# LARIX_V3_finish.net
KiCad netlist of a schematic drawn in EAGLE
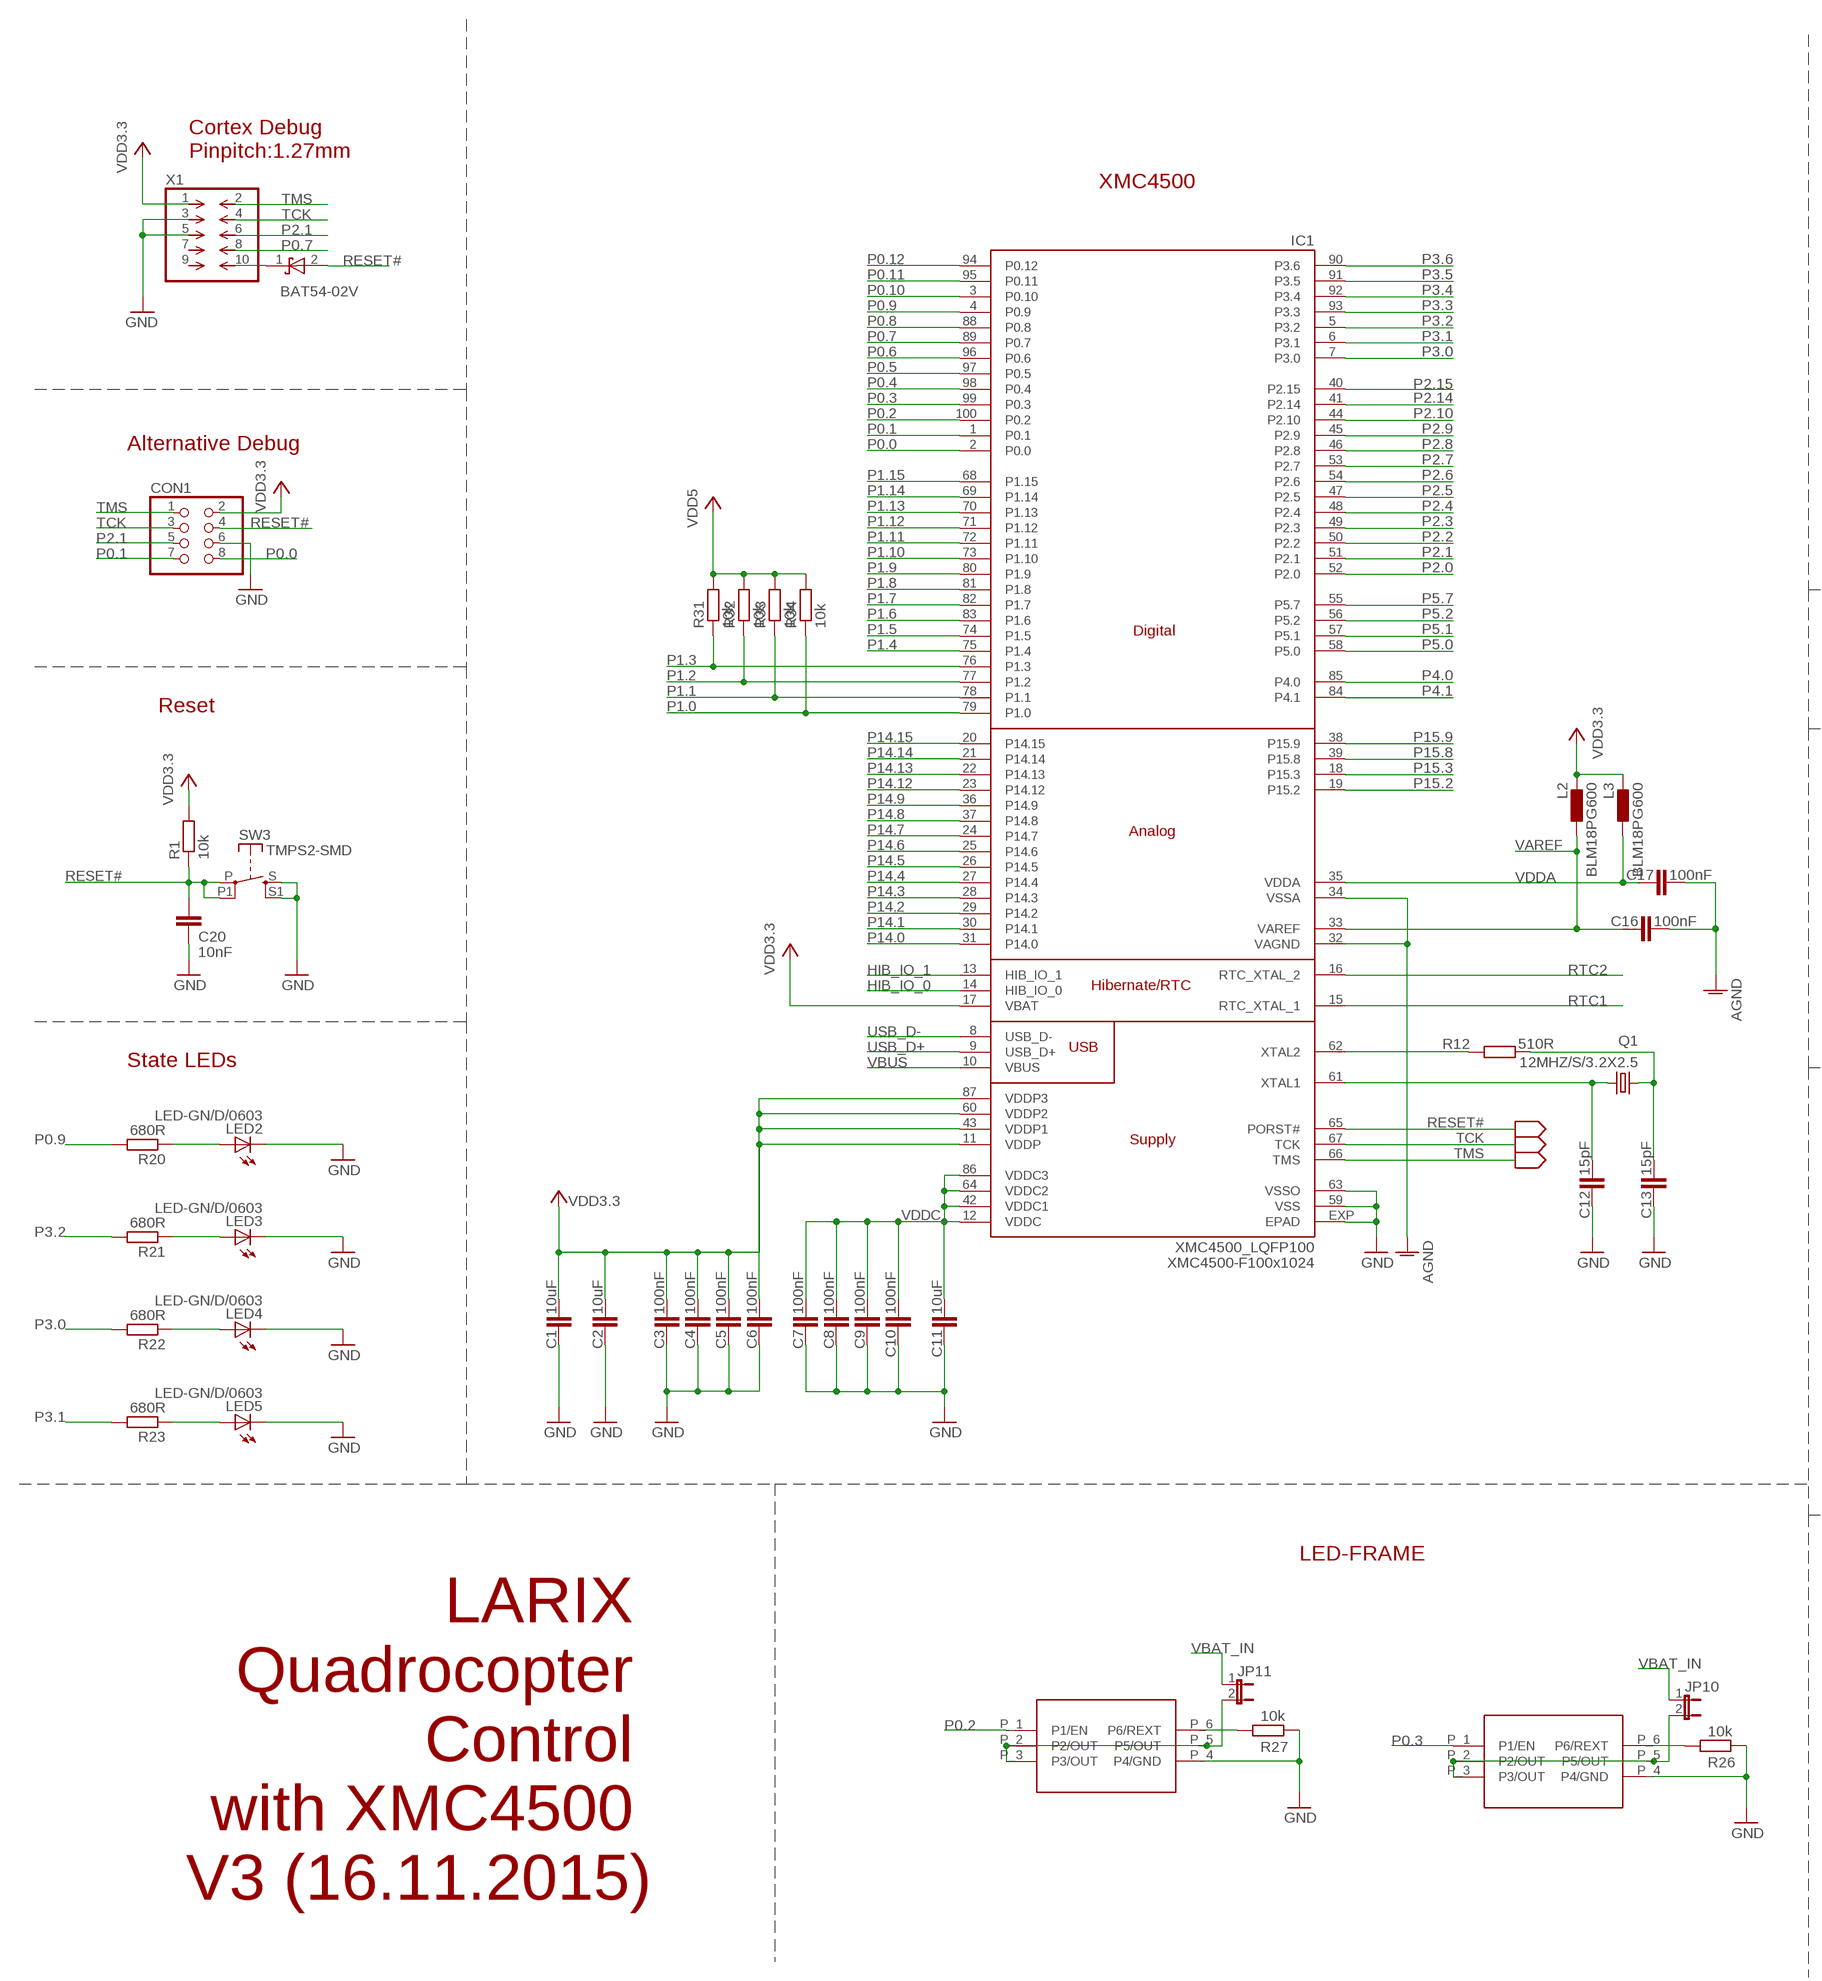
[diagram p0: schematic, sheet 1, part 1 of 2]
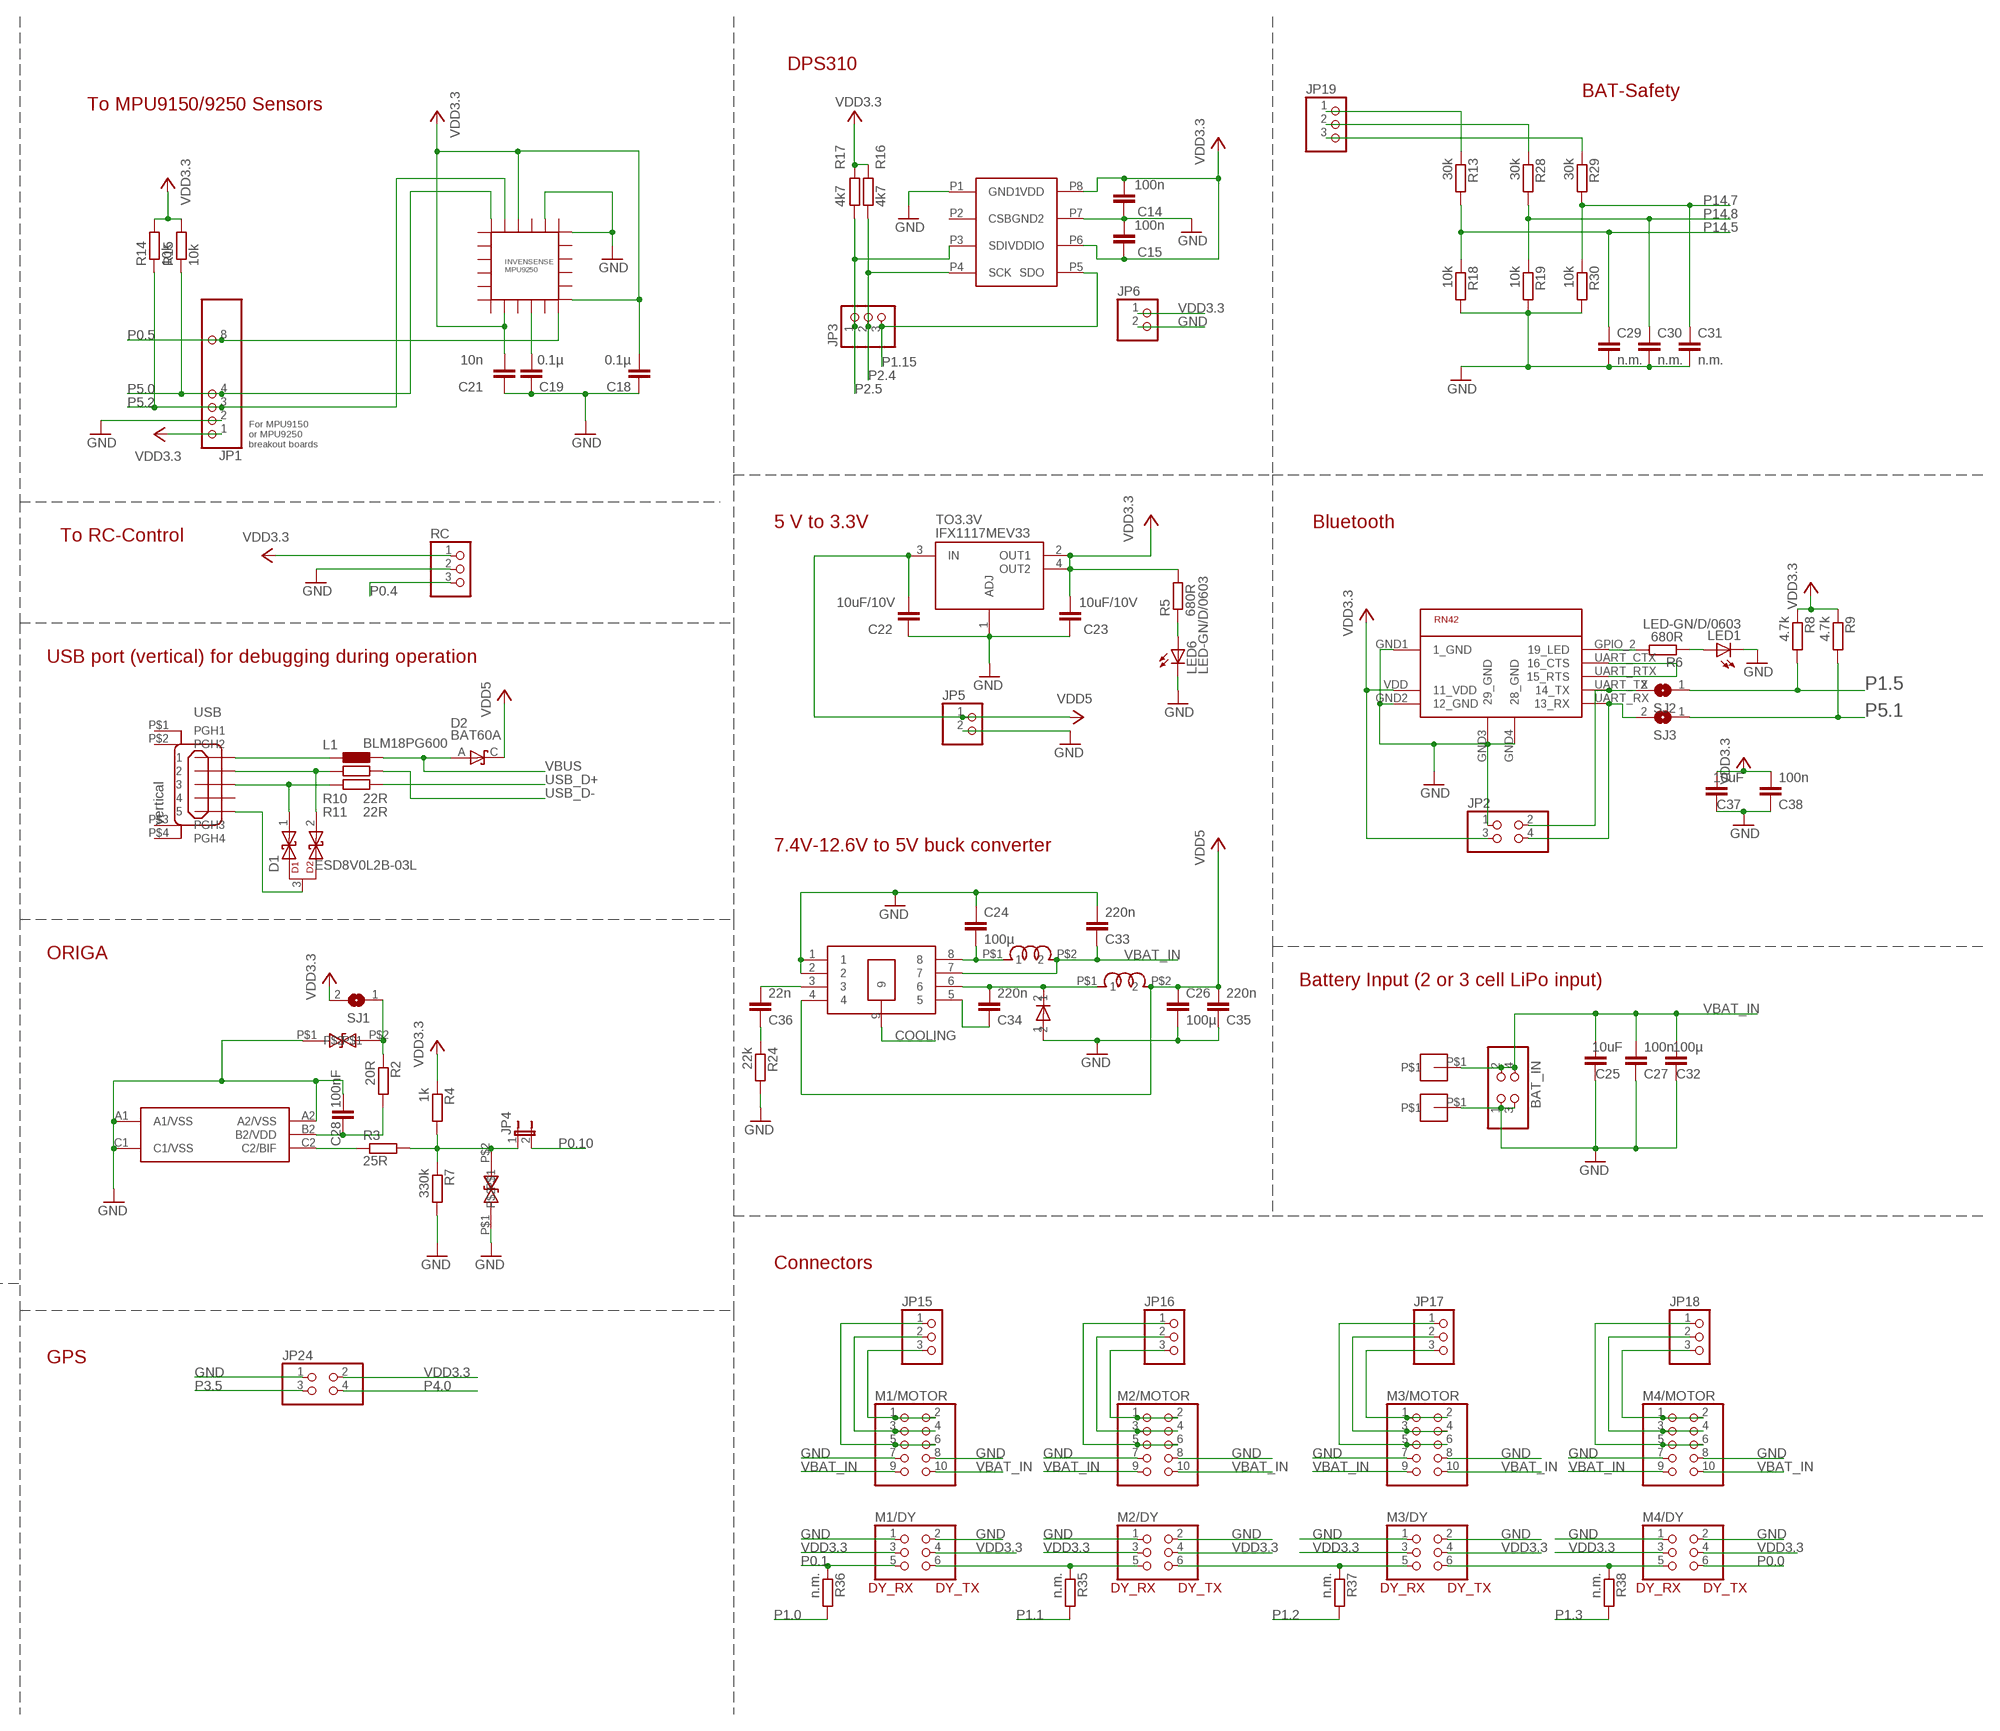
[diagram p1: schematic, sheet 1, part 2 of 2]

(export (version "E")
  (design (tool "Eeschema 10.0.6"))
  (components
    (comp (ref "47UH")
      (value "WUERTH47UFCHOKE")
      (footprint "eagle-import:INDUCTANCEWUERTZ47UH")
      (libsource (lib "eagle-import") (part "WUERTH47UFCHOKE"))
    )
    (comp (ref "47µH")
      (value "WUERTH47UFCHOKE")
      (footprint "eagle-import:INDUCTANCEWUERTZ47UH")
      (libsource (lib "eagle-import") (part "WUERTH47UFCHOKE"))
    )
    (comp (ref "BAT_IN")
      (value "PINHD-2X2")
      (footprint "eagle-import:2X02")
      (libsource (lib "eagle-import") (part "PINHD-2X2"))
    )
    (comp (ref "C1")
      (value "10uF")
      (footprint "eagle-import:C0805K")
      (libsource (lib "eagle-import") (part "C-EUC0805K"))
    )
    (comp (ref "C2")
      (value "10uF")
      (footprint "eagle-import:C0805K")
      (libsource (lib "eagle-import") (part "C-EUC0805K"))
    )
    (comp (ref "C3")
      (value "100nF")
      (footprint "eagle-import:C0603")
      (libsource (lib "eagle-import") (part "resistor_C-EUC0603"))
    )
    (comp (ref "C4")
      (value "100nF")
      (footprint "eagle-import:C0603")
      (libsource (lib "eagle-import") (part "resistor_C-EUC0603"))
    )
    (comp (ref "C5")
      (value "100nF")
      (footprint "eagle-import:C0603")
      (libsource (lib "eagle-import") (part "resistor_C-EUC0603"))
    )
    (comp (ref "C6")
      (value "100nF")
      (footprint "eagle-import:C0603")
      (libsource (lib "eagle-import") (part "resistor_C-EUC0603"))
    )
    (comp (ref "C7")
      (value "100nF")
      (footprint "eagle-import:C0603")
      (libsource (lib "eagle-import") (part "resistor_C-EUC0603"))
    )
    (comp (ref "C8")
      (value "100nF")
      (footprint "eagle-import:C0603")
      (libsource (lib "eagle-import") (part "resistor_C-EUC0603"))
    )
    (comp (ref "C9")
      (value "100nF")
      (footprint "eagle-import:C0603")
      (libsource (lib "eagle-import") (part "resistor_C-EUC0603"))
    )
    (comp (ref "C10")
      (value "100nF")
      (footprint "eagle-import:C0603")
      (libsource (lib "eagle-import") (part "resistor_C-EUC0603"))
    )
    (comp (ref "C11")
      (value "10uF")
      (footprint "eagle-import:C0805K")
      (libsource (lib "eagle-import") (part "C-EUC0805K"))
    )
    (comp (ref "C12")
      (value "15pF")
      (footprint "eagle-import:C0603")
      (libsource (lib "eagle-import") (part "resistor_C-EUC0603"))
    )
    (comp (ref "C13")
      (value "15pF")
      (footprint "eagle-import:C0603")
      (libsource (lib "eagle-import") (part "resistor_C-EUC0603"))
    )
    (comp (ref "C14")
      (value "100n")
      (footprint "eagle-import:C0603")
      (libsource (lib "eagle-import") (part "resistor_C-EUC0603"))
    )
    (comp (ref "C15")
      (value "100n")
      (footprint "eagle-import:C0603")
      (libsource (lib "eagle-import") (part "resistor_C-EUC0603"))
    )
    (comp (ref "C16")
      (value "100nF")
      (footprint "eagle-import:C0603")
      (libsource (lib "eagle-import") (part "resistor_C-EUC0603"))
    )
    (comp (ref "C17")
      (value "100nF")
      (footprint "eagle-import:C0603")
      (libsource (lib "eagle-import") (part "resistor_C-EUC0603"))
    )
    (comp (ref "C18")
      (value "0.1µ")
      (footprint "eagle-import:C0603")
      (libsource (lib "eagle-import") (part "resistor_C-EUC0603"))
    )
    (comp (ref "C19")
      (value "0.1µ")
      (footprint "eagle-import:C0603")
      (libsource (lib "eagle-import") (part "resistor_C-EUC0603"))
    )
    (comp (ref "C20")
      (value "10nF")
      (footprint "eagle-import:C0603")
      (libsource (lib "eagle-import") (part "resistor_C-EUC0603"))
    )
    (comp (ref "C21")
      (value "10n")
      (footprint "eagle-import:C0603")
      (libsource (lib "eagle-import") (part "resistor_C-EUC0603"))
    )
    (comp (ref "C22")
      (value "10uF/10V")
      (footprint "eagle-import:C0805K")
      (libsource (lib "eagle-import") (part "C-EUC0805K"))
    )
    (comp (ref "C23")
      (value "10uF/10V")
      (footprint "eagle-import:C0805K")
      (libsource (lib "eagle-import") (part "C-EUC0805K"))
    )
    (comp (ref "C24")
      (value "100µ")
      (footprint "eagle-import:C1206K")
      (libsource (lib "eagle-import") (part "resistor_C-EUC1206K"))
    )
    (comp (ref "C25")
      (value "10uF")
      (footprint "eagle-import:C0805K")
      (libsource (lib "eagle-import") (part "C-EUC0805K"))
    )
    (comp (ref "C26")
      (value "100µ")
      (footprint "eagle-import:C1206K")
      (libsource (lib "eagle-import") (part "resistor_C-EUC1206K"))
    )
    (comp (ref "C27")
      (value "100n")
      (footprint "eagle-import:C0603")
      (libsource (lib "eagle-import") (part "resistor_C-EUC0603"))
    )
    (comp (ref "C28")
      (value "100nF")
      (footprint "eagle-import:C0603")
      (libsource (lib "eagle-import") (part "resistor_C-EUC0603"))
    )
    (comp (ref "C29")
      (value "n.m.")
      (footprint "eagle-import:C0603")
      (libsource (lib "eagle-import") (part "resistor_C-EUC0603"))
    )
    (comp (ref "C30")
      (value "n.m.")
      (footprint "eagle-import:C0603")
      (libsource (lib "eagle-import") (part "resistor_C-EUC0603"))
    )
    (comp (ref "C31")
      (value "n.m.")
      (footprint "eagle-import:C0603")
      (libsource (lib "eagle-import") (part "resistor_C-EUC0603"))
    )
    (comp (ref "C32")
      (value "100µ")
      (footprint "eagle-import:C1206")
      (libsource (lib "eagle-import") (part "resistor_C-EUC1206"))
    )
    (comp (ref "C33")
      (value "220n")
      (footprint "eagle-import:C0603")
      (libsource (lib "eagle-import") (part "resistor_C-EUC0603"))
    )
    (comp (ref "C34")
      (value "220n")
      (footprint "eagle-import:C0603")
      (libsource (lib "eagle-import") (part "resistor_C-EUC0603"))
    )
    (comp (ref "C35")
      (value "220n")
      (footprint "eagle-import:C0603")
      (libsource (lib "eagle-import") (part "resistor_C-EUC0603"))
    )
    (comp (ref "C36")
      (value "22n")
      (footprint "eagle-import:C0603")
      (libsource (lib "eagle-import") (part "resistor_C-EUC0603"))
    )
    (comp (ref "C37")
      (value "10uF")
      (footprint "eagle-import:C0805K")
      (libsource (lib "eagle-import") (part "C-EUC0805K"))
    )
    (comp (ref "C38")
      (value "100n")
      (footprint "eagle-import:C0603")
      (libsource (lib "eagle-import") (part "resistor_C-EUC0603"))
    )
    (comp (ref "CON1")
      (value "PINHD-2X4")
      (footprint "eagle-import:2X04")
      (libsource (lib "eagle-import") (part "PINHD-2X4"))
    )
    (comp (ref "D1")
      (value "ESD8V0L2B-03L")
      (footprint "eagle-import:TSLP-3-1")
      (libsource (lib "eagle-import") (part "ESD8V0L2B-03L"))
    )
    (comp (ref "D2")
      (value "BAT60A")
      (footprint "eagle-import:SOD323-R")
      (libsource (lib "eagle-import") (part "BAT60"))
    )
    (comp (ref "IC1")
      (value "XMC4500_LQFP100")
      (footprint "eagle-import:P_PG-LQFP-100-11")
      (libsource (lib "eagle-import") (part "XMC4400_LQFP100"))
    )
    (comp (ref "IC2")
      (value "INVENSENSE9250EHERBY")
      (footprint "eagle-import:QFN3X3-24+")
      (libsource (lib "eagle-import") (part "INVENSENSE9250HERBYE"))
    )
    (comp (ref "JP1")
      (value "PINHD-1X10")
      (footprint "eagle-import:1X10")
      (libsource (lib "eagle-import") (part "PINHD-1X10"))
    )
    (comp (ref "JP2")
      (value "PINHD-2X2")
      (footprint "eagle-import:2X02")
      (libsource (lib "eagle-import") (part "PINHD-2X2"))
    )
    (comp (ref "JP3")
      (value "PINHD-1X3")
      (footprint "eagle-import:1X03")
      (libsource (lib "eagle-import") (part "PINHD-1X3"))
    )
    (comp (ref "JP4")
      (value "JP1E")
      (footprint "eagle-import:JP1")
      (libsource (lib "eagle-import") (part "JP1E"))
    )
    (comp (ref "JP5")
      (value "PINHD-1X2")
      (footprint "eagle-import:1X02")
      (libsource (lib "eagle-import") (part "PINHD-1X2"))
    )
    (comp (ref "JP6")
      (value "PINHD-1X2")
      (footprint "eagle-import:1X02")
      (libsource (lib "eagle-import") (part "PINHD-1X2"))
    )
    (comp (ref "JP10")
      (value "JP1E")
      (footprint "eagle-import:JP1")
      (libsource (lib "eagle-import") (part "JP1E"))
    )
    (comp (ref "JP11")
      (value "JP1E")
      (footprint "eagle-import:JP1")
      (libsource (lib "eagle-import") (part "JP1E"))
    )
    (comp (ref "JP15")
      (value "PINHD-1X3")
      (footprint "eagle-import:1X03")
      (libsource (lib "eagle-import") (part "PINHD-1X3"))
    )
    (comp (ref "JP16")
      (value "PINHD-1X3")
      (footprint "eagle-import:1X03")
      (libsource (lib "eagle-import") (part "PINHD-1X3"))
    )
    (comp (ref "JP17")
      (value "PINHD-1X3")
      (footprint "eagle-import:1X03")
      (libsource (lib "eagle-import") (part "PINHD-1X3"))
    )
    (comp (ref "JP18")
      (value "PINHD-1X3")
      (footprint "eagle-import:1X03")
      (libsource (lib "eagle-import") (part "PINHD-1X3"))
    )
    (comp (ref "JP19")
      (value "PINHD-1X3")
      (footprint "eagle-import:1X03")
      (libsource (lib "eagle-import") (part "PINHD-1X3"))
    )
    (comp (ref "JP24")
      (value "PINHD-2X2")
      (footprint "eagle-import:2X02")
      (libsource (lib "eagle-import") (part "PINHD-2X2"))
    )
    (comp (ref "L1")
      (value "BLM18PG600")
      (footprint "eagle-import:L1608")
      (libsource (lib "eagle-import") (part "L_EU_L0603"))
    )
    (comp (ref "L2")
      (value "BLM18PG600")
      (footprint "eagle-import:L1608")
      (libsource (lib "eagle-import") (part "L_EU_L0603"))
    )
    (comp (ref "L3")
      (value "BLM18PG600")
      (footprint "eagle-import:L1608")
      (libsource (lib "eagle-import") (part "L_EU_L0603"))
    )
    (comp (ref "LED1")
      (value "LED-GN/D/0603")
      (footprint "eagle-import:CHIPLED_0603")
      (libsource (lib "eagle-import") (part "LEDCHIPLED_0603"))
    )
    (comp (ref "LED2")
      (value "LED-GN/D/0603")
      (footprint "eagle-import:CHIPLED_0603")
      (libsource (lib "eagle-import") (part "LEDCHIPLED_0603"))
    )
    (comp (ref "LED3")
      (value "LED-GN/D/0603")
      (footprint "eagle-import:CHIPLED_0603")
      (libsource (lib "eagle-import") (part "LEDCHIPLED_0603"))
    )
    (comp (ref "LED4")
      (value "LED-GN/D/0603")
      (footprint "eagle-import:CHIPLED_0603")
      (libsource (lib "eagle-import") (part "LEDCHIPLED_0603"))
    )
    (comp (ref "LED5")
      (value "LED-GN/D/0603")
      (footprint "eagle-import:CHIPLED_0603")
      (libsource (lib "eagle-import") (part "LEDCHIPLED_0603"))
    )
    (comp (ref "LED6")
      (value "LED-GN/D/0603")
      (footprint "eagle-import:CHIPLED_0603")
      (libsource (lib "eagle-import") (part "LEDCHIPLED_0603"))
    )
    (comp (ref "M1/DY")
      (value "PINHD-2X3")
      (footprint "eagle-import:2X03")
      (libsource (lib "eagle-import") (part "PINHD-2X3"))
    )
    (comp (ref "M1/MOTOR")
      (value "PINHD-2X5")
      (footprint "eagle-import:2X05")
      (libsource (lib "eagle-import") (part "PINHD-2X5"))
    )
    (comp (ref "M2/DY")
      (value "PINHD-2X3")
      (footprint "eagle-import:2X03")
      (libsource (lib "eagle-import") (part "PINHD-2X3"))
    )
    (comp (ref "M2/MOTOR")
      (value "PINHD-2X5")
      (footprint "eagle-import:2X05")
      (libsource (lib "eagle-import") (part "PINHD-2X5"))
    )
    (comp (ref "M3/DY")
      (value "PINHD-2X3")
      (footprint "eagle-import:2X03")
      (libsource (lib "eagle-import") (part "PINHD-2X3"))
    )
    (comp (ref "M3/MOTOR")
      (value "PINHD-2X5")
      (footprint "eagle-import:2X05")
      (libsource (lib "eagle-import") (part "PINHD-2X5"))
    )
    (comp (ref "M4/DY")
      (value "PINHD-2X3")
      (footprint "eagle-import:2X03")
      (libsource (lib "eagle-import") (part "PINHD-2X3"))
    )
    (comp (ref "M4/MOTOR")
      (value "PINHD-2X5")
      (footprint "eagle-import:2X05")
      (libsource (lib "eagle-import") (part "PINHD-2X5"))
    )
    (comp (ref "Q1")
      (value "12MHZ/S/3.2X2.5")
      (footprint "eagle-import:32X25_4PAD")
      (libsource (lib "eagle-import") (part "NX3225_2"))
    )
    (comp (ref "R1")
      (value "10k")
      (footprint "eagle-import:R0603")
      (libsource (lib "eagle-import") (part "resistor_R-EU_R0603"))
    )
    (comp (ref "R2")
      (value "20R")
      (footprint "eagle-import:R0603")
      (libsource (lib "eagle-import") (part "R-EU_R0603"))
    )
    (comp (ref "R3")
      (value "25R")
      (footprint "eagle-import:R0603")
      (libsource (lib "eagle-import") (part "R-EU_R0603"))
    )
    (comp (ref "R4")
      (value "1k")
      (footprint "eagle-import:R0603")
      (libsource (lib "eagle-import") (part "R-EU_R0603"))
    )
    (comp (ref "R5")
      (value "680R")
      (footprint "eagle-import:R0603")
      (libsource (lib "eagle-import") (part "R-EU_R0603"))
    )
    (comp (ref "R6")
      (value "680R")
      (footprint "eagle-import:R0603")
      (libsource (lib "eagle-import") (part "R-EU_R0603"))
    )
    (comp (ref "R7")
      (value "330k")
      (footprint "eagle-import:R0603")
      (libsource (lib "eagle-import") (part "R-EU_R0603"))
    )
    (comp (ref "R8")
      (value "4.7k")
      (footprint "eagle-import:R0603")
      (libsource (lib "eagle-import") (part "R-EU_R0603"))
    )
    (comp (ref "R9")
      (value "4.7k")
      (footprint "eagle-import:R0603")
      (libsource (lib "eagle-import") (part "R-EU_R0603"))
    )
    (comp (ref "R10")
      (value "22R")
      (footprint "eagle-import:R0603")
      (libsource (lib "eagle-import") (part "resistor_R-EU_R0603"))
    )
    (comp (ref "R11")
      (value "22R")
      (footprint "eagle-import:R0603")
      (libsource (lib "eagle-import") (part "resistor_R-EU_R0603"))
    )
    (comp (ref "R12")
      (value "510R")
      (footprint "eagle-import:R0603")
      (libsource (lib "eagle-import") (part "R-EU_R0603"))
    )
    (comp (ref "R13")
      (value "30k")
      (footprint "eagle-import:R0603")
      (libsource (lib "eagle-import") (part "R-EU_R0603"))
    )
    (comp (ref "R14")
      (value "10k")
      (footprint "eagle-import:R0603")
      (libsource (lib "eagle-import") (part "resistor_R-EU_R0603"))
    )
    (comp (ref "R15")
      (value "10k")
      (footprint "eagle-import:R0603")
      (libsource (lib "eagle-import") (part "resistor_R-EU_R0603"))
    )
    (comp (ref "R16")
      (value "4k7")
      (footprint "eagle-import:R0603")
      (libsource (lib "eagle-import") (part "resistor_R-EU_R0603"))
    )
    (comp (ref "R17")
      (value "4k7")
      (footprint "eagle-import:R0603")
      (libsource (lib "eagle-import") (part "resistor_R-EU_R0603"))
    )
    (comp (ref "R18")
      (value "10k")
      (footprint "eagle-import:R0603")
      (libsource (lib "eagle-import") (part "R-EU_R0603"))
    )
    (comp (ref "R19")
      (value "10k")
      (footprint "eagle-import:R0603")
      (libsource (lib "eagle-import") (part "R-EU_R0603"))
    )
    (comp (ref "R20")
      (value "680R")
      (footprint "eagle-import:R0603")
      (libsource (lib "eagle-import") (part "R-EU_R0603"))
    )
    (comp (ref "R21")
      (value "680R")
      (footprint "eagle-import:R0603")
      (libsource (lib "eagle-import") (part "R-EU_R0603"))
    )
    (comp (ref "R22")
      (value "680R")
      (footprint "eagle-import:R0603")
      (libsource (lib "eagle-import") (part "R-EU_R0603"))
    )
    (comp (ref "R23")
      (value "680R")
      (footprint "eagle-import:R0603")
      (libsource (lib "eagle-import") (part "R-EU_R0603"))
    )
    (comp (ref "R24")
      (value "22k")
      (footprint "eagle-import:R0603")
      (libsource (lib "eagle-import") (part "R-EU_R0603"))
    )
    (comp (ref "R26")
      (value "10k")
      (footprint "eagle-import:R0603")
      (libsource (lib "eagle-import") (part "resistor_R-EU_R0603"))
    )
    (comp (ref "R27")
      (value "10k")
      (footprint "eagle-import:R0603")
      (libsource (lib "eagle-import") (part "resistor_R-EU_R0603"))
    )
    (comp (ref "R28")
      (value "30k")
      (footprint "eagle-import:R0603")
      (libsource (lib "eagle-import") (part "R-EU_R0603"))
    )
    (comp (ref "R29")
      (value "30k")
      (footprint "eagle-import:R0603")
      (libsource (lib "eagle-import") (part "R-EU_R0603"))
    )
    (comp (ref "R30")
      (value "10k")
      (footprint "eagle-import:R0603")
      (libsource (lib "eagle-import") (part "R-EU_R0603"))
    )
    (comp (ref "R31")
      (value "10k")
      (footprint "eagle-import:R0603")
      (libsource (lib "eagle-import") (part "resistor_R-EU_R0603"))
    )
    (comp (ref "R32")
      (value "10k")
      (footprint "eagle-import:R0603")
      (libsource (lib "eagle-import") (part "resistor_R-EU_R0603"))
    )
    (comp (ref "R33")
      (value "10k")
      (footprint "eagle-import:R0603")
      (libsource (lib "eagle-import") (part "resistor_R-EU_R0603"))
    )
    (comp (ref "R34")
      (value "10k")
      (footprint "eagle-import:R0603")
      (libsource (lib "eagle-import") (part "resistor_R-EU_R0603"))
    )
    (comp (ref "R35")
      (value "n.m.")
      (footprint "eagle-import:R0603")
      (libsource (lib "eagle-import") (part "R-EU_R0603"))
    )
    (comp (ref "R36")
      (value "n.m.")
      (footprint "eagle-import:R0603")
      (libsource (lib "eagle-import") (part "R-EU_R0603"))
    )
    (comp (ref "R37")
      (value "n.m.")
      (footprint "eagle-import:R0603")
      (libsource (lib "eagle-import") (part "R-EU_R0603"))
    )
    (comp (ref "R38")
      (value "n.m.")
      (footprint "eagle-import:R0603")
      (libsource (lib "eagle-import") (part "R-EU_R0603"))
    )
    (comp (ref "RC")
      (value "PINHD-1X3")
      (footprint "eagle-import:1X03")
      (libsource (lib "eagle-import") (part "PINHD-1X3"))
    )
    (comp (ref "SJ1") (value "SJ") (footprint "eagle-import:SJ") (libsource (lib "eagle-import") (part "SJ")))
    (comp (ref "SJ2") (value "SJ") (footprint "eagle-import:SJ") (libsource (lib "eagle-import") (part "SJ")))
    (comp (ref "SJ3") (value "SJ") (footprint "eagle-import:SJ") (libsource (lib "eagle-import") (part "SJ")))
    (comp (ref "SW3")
      (value "TMPS2-SMD")
      (footprint "eagle-import:FSM2JSMA")
      (libsource (lib "eagle-import") (part "FSM2JSMA"))
    )
    (comp (ref "TO3.3V")
      (value "IFX1117MEV33")
      (footprint "eagle-import:SOT223")
      (libsource (lib "eagle-import") (part "IFX1117"))
    )
    (comp (ref "U$7")
      (value "INF-PG-DSO-8-27_N_1")
      (footprint "eagle-import:INF-PG-DSO-8-27_N_1PRIMARY")
      (libsource (lib "eagle-import") (part "INF-PG-DSO-8-27_N_1"))
    )
    (comp (ref "U$8")
      (value "DPS310DRUCKSENSOR")
      (footprint "eagle-import:LGA8R125P0X4_500X300X120")
      (libsource (lib "eagle-import") (part "DPS310DRUCKSENSOR"))
    )
    (comp (ref "U$9")
      (value "ESD218-B1-02EL")
      (footprint "eagle-import:TSLP-2-20")
      (libsource (lib "eagle-import") (part "ESD218-B1-02EL"))
    )
    (comp (ref "U$11")
      (value "ORIGA2L")
      (footprint "eagle-import:WLB-5")
      (libsource (lib "eagle-import") (part "ORIGA2L"))
    )
    (comp (ref "U$12")
      (value "PAD-BATTERY")
      (footprint "eagle-import:BATT-SOLDER")
      (libsource (lib "eagle-import") (part "PAD-BATTERY"))
    )
    (comp (ref "U$13")
      (value "BLUETOOTHRN42+SHIELD")
      (footprint "eagle-import:RN42+SHIELD")
      (libsource (lib "eagle-import") (part "BLUETOOTHRN42+SHIELD"))
    )
    (comp (ref "U$14")
      (value "PAD-BATTERY")
      (footprint "eagle-import:BATT-SOLDER")
      (libsource (lib "eagle-import") (part "PAD-BATTERY"))
    )
    (comp (ref "U$16")
      (value "INF-SOD323_V_1")
      (footprint "eagle-import:INF-SOD323_V_1PRIMARY")
      (libsource (lib "eagle-import") (part "INF-SOD323_V_1"))
    )
    (comp (ref "U$18")
      (value "BCU320")
      (footprint "eagle-import:SC74")
      (libsource (lib "eagle-import") (part "BCU320"))
    )
    (comp (ref "U$20")
      (value "BCU320")
      (footprint "eagle-import:SC74")
      (libsource (lib "eagle-import") (part "BCU320"))
    )
    (comp (ref "U$22")
      (value "ESD218-B1-02EL")
      (footprint "eagle-import:TSLP-2-20")
      (libsource (lib "eagle-import") (part "ESD218-B1-02EL"))
    )
    (comp (ref "USB")
      (value "vertical")
      (footprint "eagle-import:USBVERTICAL")
      (libsource (lib "eagle-import") (part "MICRO_USB_VERTICAL"))
    )
    (comp (ref "V1")
      (value "BAT54-02V")
      (footprint "eagle-import:SC79")
      (libsource (lib "eagle-import") (part "BAT54-02V"))
    )
    (comp (ref "X1")
      (value "FTSH-105-01-F-D-K")
      (footprint "eagle-import:FTSH-105-01-F-D-K")
      (libsource (lib "eagle-import") (part "FTSH-105-01-F-D-K"))
    )
  )
  (nets
    (net (code "1") (name "/COOLING") (class "Default")
      (node (ref "U$7") (pin "9") (pinfunction "9_9") (pintype "bidirectional"))
    )
    (net (code "2") (name "/HIB_IO_0") (class "Default")
      (node (ref "IC1") (pin "14") (pinfunction "HIB_IO_0_14") (pintype "bidirectional"))
    )
    (net (code "3") (name "/HIB_IO_1") (class "Default")
      (node (ref "IC1") (pin "13") (pinfunction "HIB_IO_1_13") (pintype "bidirectional"))
    )
    (net (code "4") (name "/P0.0") (class "Default")
      (node (ref "CON1") (pin "8") (pinfunction "8_8") (pintype "passive"))
      (node (ref "IC1") (pin "2") (pinfunction "P0.0_2") (pintype "bidirectional"))
      (node (ref "M4/DY") (pin "6") (pinfunction "6_6") (pintype "passive"))
    )
    (net (code "5") (name "/P0.1") (class "Default")
      (node (ref "CON1") (pin "7") (pinfunction "7_7") (pintype "passive"))
      (node (ref "IC1") (pin "1") (pinfunction "P0.1_1") (pintype "bidirectional"))
      (node (ref "M1/DY") (pin "5") (pinfunction "5_5") (pintype "passive"))
      (node (ref "R36") (pin "1") (pinfunction "1_1") (pintype "passive"))
    )
    (net (code "6") (name "/P0.2") (class "Default")
      (node (ref "IC1") (pin "100") (pinfunction "P0.2_100") (pintype "bidirectional"))
      (node (ref "U$20") (pin "P_1") (pinfunction "P1/EN_P_1") (pintype "bidirectional"))
    )
    (net (code "7") (name "/P0.3") (class "Default")
      (node (ref "IC1") (pin "99") (pinfunction "P0.3_99") (pintype "bidirectional"))
      (node (ref "U$18") (pin "P_1") (pinfunction "P1/EN_P_1") (pintype "bidirectional"))
    )
    (net (code "8") (name "/P0.4") (class "Default")
      (node (ref "IC1") (pin "98") (pinfunction "P0.4_98") (pintype "bidirectional"))
      (node (ref "RC") (pin "3") (pinfunction "3_3") (pintype "passive"))
    )
    (net (code "9") (name "/P0.5") (class "Default")
      (node (ref "IC1") (pin "97") (pinfunction "P0.5_97") (pintype "bidirectional"))
      (node (ref "IC2") (pin "12") (pinfunction "12_12") (pintype "bidirectional"))
      (node (ref "JP1") (pin "8") (pinfunction "8_8") (pintype "passive"))
    )
    (net (code "10") (name "/P0.6") (class "Default")
      (node (ref "IC1") (pin "96") (pinfunction "P0.6_96") (pintype "bidirectional"))
    )
    (net (code "11") (name "/P0.7") (class "Default")
      (node (ref "IC1") (pin "89") (pinfunction "P0.7_89") (pintype "bidirectional"))
      (node (ref "X1") (pin "8") (pinfunction "8_8") (pintype "passive"))
    )
    (net (code "12") (name "/P0.8") (class "Default")
      (node (ref "IC1") (pin "88") (pinfunction "P0.8_88") (pintype "bidirectional"))
    )
    (net (code "13") (name "/P0.9") (class "Default")
      (node (ref "IC1") (pin "4") (pinfunction "P0.9_4") (pintype "bidirectional"))
      (node (ref "R20") (pin "2") (pinfunction "2_2") (pintype "passive"))
    )
    (net (code "14") (name "/P0.10") (class "Default")
      (node (ref "IC1") (pin "3") (pinfunction "P0.10_3") (pintype "bidirectional"))
      (node (ref "JP4") (pin "2") (pinfunction "2_2") (pintype "passive"))
    )
    (net (code "15") (name "/P0.11") (class "Default")
      (node (ref "IC1") (pin "95") (pinfunction "P0.11_95") (pintype "bidirectional"))
    )
    (net (code "16") (name "/P0.12") (class "Default")
      (node (ref "IC1") (pin "94") (pinfunction "P0.12_94") (pintype "bidirectional"))
    )
    (net (code "17") (name "/P1.0") (class "Default")
      (node (ref "IC1") (pin "79") (pinfunction "P1.0_79") (pintype "bidirectional"))
      (node (ref "R34") (pin "1") (pinfunction "1_1") (pintype "passive"))
      (node (ref "R36") (pin "2") (pinfunction "2_2") (pintype "passive"))
    )
    (net (code "18") (name "/P1.1") (class "Default")
      (node (ref "IC1") (pin "78") (pinfunction "P1.1_78") (pintype "bidirectional"))
      (node (ref "R33") (pin "1") (pinfunction "1_1") (pintype "passive"))
      (node (ref "R35") (pin "2") (pinfunction "2_2") (pintype "passive"))
    )
    (net (code "19") (name "/P1.2") (class "Default")
      (node (ref "IC1") (pin "77") (pinfunction "P1.2_77") (pintype "bidirectional"))
      (node (ref "R32") (pin "1") (pinfunction "1_1") (pintype "passive"))
      (node (ref "R37") (pin "2") (pinfunction "2_2") (pintype "passive"))
    )
    (net (code "20") (name "/P1.3") (class "Default")
      (node (ref "IC1") (pin "76") (pinfunction "P1.3_76") (pintype "bidirectional"))
      (node (ref "R31") (pin "1") (pinfunction "1_1") (pintype "passive"))
      (node (ref "R38") (pin "2") (pinfunction "2_2") (pintype "passive"))
    )
    (net (code "21") (name "/P1.4") (class "Default")
      (node (ref "IC1") (pin "75") (pinfunction "P1.4_75") (pintype "bidirectional"))
    )
    (net (code "22") (name "/P1.5") (class "Default")
      (node (ref "IC1") (pin "74") (pinfunction "P1.5_74") (pintype "bidirectional"))
      (node (ref "R8") (pin "2") (pinfunction "2_2") (pintype "passive"))
      (node (ref "SJ2") (pin "1") (pinfunction "1_1") (pintype "passive"))
    )
    (net (code "23") (name "/P1.6") (class "Default")
      (node (ref "IC1") (pin "83") (pinfunction "P1.6_83") (pintype "bidirectional"))
    )
    (net (code "24") (name "/P1.7") (class "Default")
      (node (ref "IC1") (pin "82") (pinfunction "P1.7_82") (pintype "bidirectional"))
    )
    (net (code "25") (name "/P1.8") (class "Default")
      (node (ref "IC1") (pin "81") (pinfunction "P1.8_81") (pintype "bidirectional"))
    )
    (net (code "26") (name "/P1.9") (class "Default")
      (node (ref "IC1") (pin "80") (pinfunction "P1.9_80") (pintype "bidirectional"))
    )
    (net (code "27") (name "/P1.10") (class "Default")
      (node (ref "IC1") (pin "73") (pinfunction "P1.10_73") (pintype "bidirectional"))
    )
    (net (code "28") (name "/P1.11") (class "Default")
      (node (ref "IC1") (pin "72") (pinfunction "P1.11_72") (pintype "bidirectional"))
    )
    (net (code "29") (name "/P1.12") (class "Default")
      (node (ref "IC1") (pin "71") (pinfunction "P1.12_71") (pintype "bidirectional"))
    )
    (net (code "30") (name "/P1.13") (class "Default")
      (node (ref "IC1") (pin "70") (pinfunction "P1.13_70") (pintype "bidirectional"))
    )
    (net (code "31") (name "/P1.14") (class "Default")
      (node (ref "IC1") (pin "69") (pinfunction "P1.14_69") (pintype "bidirectional"))
    )
    (net (code "32") (name "/P1.15") (class "Default")
      (node (ref "IC1") (pin "68") (pinfunction "P1.15_68") (pintype "bidirectional"))
      (node (ref "JP3") (pin "3") (pinfunction "3_3") (pintype "passive"))
      (node (ref "U$8") (pin "P5") (pinfunction "SDO_P5") (pintype "bidirectional"))
    )
    (net (code "33") (name "/P2.0") (class "Default")
      (node (ref "IC1") (pin "52") (pinfunction "P2.0_52") (pintype "bidirectional"))
    )
    (net (code "34") (name "/P2.1") (class "Default")
      (node (ref "CON1") (pin "5") (pinfunction "5_5") (pintype "passive"))
      (node (ref "IC1") (pin "51") (pinfunction "P2.1_51") (pintype "bidirectional"))
      (node (ref "X1") (pin "6") (pinfunction "6_6") (pintype "passive"))
    )
    (net (code "35") (name "/P2.2") (class "Default")
      (node (ref "IC1") (pin "50") (pinfunction "P2.2_50") (pintype "bidirectional"))
    )
    (net (code "36") (name "/P2.3") (class "Default")
      (node (ref "IC1") (pin "49") (pinfunction "P2.3_49") (pintype "bidirectional"))
    )
    (net (code "37") (name "/P2.4") (class "Default")
      (node (ref "IC1") (pin "48") (pinfunction "P2.4_48") (pintype "bidirectional"))
      (node (ref "JP3") (pin "2") (pinfunction "2_2") (pintype "passive"))
      (node (ref "R16") (pin "2") (pinfunction "2_2") (pintype "passive"))
      (node (ref "U$8") (pin "P4") (pinfunction "SCK_P4") (pintype "bidirectional"))
    )
    (net (code "38") (name "/P2.5") (class "Default")
      (node (ref "IC1") (pin "47") (pinfunction "P2.5_47") (pintype "bidirectional"))
      (node (ref "JP3") (pin "1") (pinfunction "1_1") (pintype "passive"))
      (node (ref "R17") (pin "2") (pinfunction "2_2") (pintype "passive"))
      (node (ref "U$8") (pin "P3") (pinfunction "SDI_P3") (pintype "bidirectional"))
    )
    (net (code "39") (name "/P2.6") (class "Default")
      (node (ref "IC1") (pin "54") (pinfunction "P2.6_54") (pintype "bidirectional"))
    )
    (net (code "40") (name "/P2.7") (class "Default")
      (node (ref "IC1") (pin "53") (pinfunction "P2.7_53") (pintype "bidirectional"))
    )
    (net (code "41") (name "/P2.8") (class "Default")
      (node (ref "IC1") (pin "46") (pinfunction "P2.8_46") (pintype "bidirectional"))
    )
    (net (code "42") (name "/P2.9") (class "Default")
      (node (ref "IC1") (pin "45") (pinfunction "P2.9_45") (pintype "bidirectional"))
    )
    (net (code "43") (name "/P2.10") (class "Default")
      (node (ref "IC1") (pin "44") (pinfunction "P2.10_44") (pintype "bidirectional"))
    )
    (net (code "44") (name "/P2.14") (class "Default")
      (node (ref "IC1") (pin "41") (pinfunction "P2.14_41") (pintype "bidirectional"))
    )
    (net (code "45") (name "/P2.15") (class "Default")
      (node (ref "IC1") (pin "40") (pinfunction "P2.15_40") (pintype "bidirectional"))
    )
    (net (code "46") (name "/P3.0") (class "Default")
      (node (ref "IC1") (pin "7") (pinfunction "P3.0_7") (pintype "bidirectional"))
      (node (ref "R22") (pin "2") (pinfunction "2_2") (pintype "passive"))
    )
    (net (code "47") (name "/P3.1") (class "Default")
      (node (ref "IC1") (pin "6") (pinfunction "P3.1_6") (pintype "bidirectional"))
      (node (ref "R23") (pin "2") (pinfunction "2_2") (pintype "passive"))
    )
    (net (code "48") (name "/P3.2") (class "Default")
      (node (ref "IC1") (pin "5") (pinfunction "P3.2_5") (pintype "bidirectional"))
      (node (ref "R21") (pin "2") (pinfunction "2_2") (pintype "passive"))
    )
    (net (code "49") (name "/P3.3") (class "Default")
      (node (ref "IC1") (pin "93") (pinfunction "P3.3_93") (pintype "bidirectional"))
    )
    (net (code "50") (name "/P3.4") (class "Default")
      (node (ref "IC1") (pin "92") (pinfunction "P3.4_92") (pintype "bidirectional"))
    )
    (net (code "51") (name "/P3.5") (class "Default")
      (node (ref "IC1") (pin "91") (pinfunction "P3.5_91") (pintype "bidirectional"))
      (node (ref "JP24") (pin "3") (pinfunction "3_3") (pintype "passive"))
    )
    (net (code "52") (name "/P3.6") (class "Default")
      (node (ref "IC1") (pin "90") (pinfunction "P3.6_90") (pintype "bidirectional"))
    )
    (net (code "53") (name "/P4.0") (class "Default")
      (node (ref "IC1") (pin "85") (pinfunction "P4.0_85") (pintype "bidirectional"))
      (node (ref "JP24") (pin "4") (pinfunction "4_4") (pintype "passive"))
    )
    (net (code "54") (name "/P4.1") (class "Default")
      (node (ref "IC1") (pin "84") (pinfunction "P4.1_84") (pintype "bidirectional"))
    )
    (net (code "55") (name "/P5.0") (class "Default")
      (node (ref "IC1") (pin "58") (pinfunction "P5.0_58") (pintype "bidirectional"))
      (node (ref "IC2") (pin "24") (pinfunction "24_24") (pintype "bidirectional"))
      (node (ref "JP1") (pin "4") (pinfunction "4_4") (pintype "passive"))
      (node (ref "R15") (pin "1") (pinfunction "1_1") (pintype "passive"))
    )
    (net (code "56") (name "/P5.1") (class "Default")
      (node (ref "IC1") (pin "57") (pinfunction "P5.1_57") (pintype "bidirectional"))
      (node (ref "R9") (pin "2") (pinfunction "2_2") (pintype "passive"))
      (node (ref "SJ3") (pin "1") (pinfunction "1_1") (pintype "passive"))
    )
    (net (code "57") (name "/P5.2") (class "Default")
      (node (ref "IC1") (pin "56") (pinfunction "P5.2_56") (pintype "bidirectional"))
      (node (ref "IC2") (pin "23") (pinfunction "23_23") (pintype "bidirectional"))
      (node (ref "JP1") (pin "3") (pinfunction "3_3") (pintype "passive"))
      (node (ref "R14") (pin "1") (pinfunction "1_1") (pintype "passive"))
    )
    (net (code "58") (name "/P5.7") (class "Default")
      (node (ref "IC1") (pin "55") (pinfunction "P5.7_55") (pintype "bidirectional"))
    )
    (net (code "59") (name "/P14.0") (class "Default")
      (node (ref "IC1") (pin "31") (pinfunction "P14.0_31") (pintype "bidirectional"))
    )
    (net (code "60") (name "/P14.1") (class "Default")
      (node (ref "IC1") (pin "30") (pinfunction "P14.1_30") (pintype "bidirectional"))
    )
    (net (code "61") (name "/P14.2") (class "Default")
      (node (ref "IC1") (pin "29") (pinfunction "P14.2_29") (pintype "bidirectional"))
    )
    (net (code "62") (name "/P14.3") (class "Default")
      (node (ref "IC1") (pin "28") (pinfunction "P14.3_28") (pintype "bidirectional"))
    )
    (net (code "63") (name "/P14.4") (class "Default")
      (node (ref "IC1") (pin "27") (pinfunction "P14.4_27") (pintype "bidirectional"))
    )
    (net (code "64") (name "/P14.5") (class "Default")
      (node (ref "C29") (pin "1") (pinfunction "1_1") (pintype "passive"))
      (node (ref "IC1") (pin "26") (pinfunction "P14.5_26") (pintype "bidirectional"))
      (node (ref "R13") (pin "2") (pinfunction "2_2") (pintype "passive"))
      (node (ref "R18") (pin "1") (pinfunction "1_1") (pintype "passive"))
    )
    (net (code "65") (name "/P14.6") (class "Default")
      (node (ref "IC1") (pin "25") (pinfunction "P14.6_25") (pintype "bidirectional"))
    )
    (net (code "66") (name "/P14.7") (class "Default")
      (node (ref "C31") (pin "1") (pinfunction "1_1") (pintype "passive"))
      (node (ref "IC1") (pin "24") (pinfunction "P14.7_24") (pintype "bidirectional"))
      (node (ref "R29") (pin "2") (pinfunction "2_2") (pintype "passive"))
      (node (ref "R30") (pin "1") (pinfunction "1_1") (pintype "passive"))
    )
    (net (code "67") (name "/P14.8") (class "Default")
      (node (ref "C30") (pin "1") (pinfunction "1_1") (pintype "passive"))
      (node (ref "IC1") (pin "37") (pinfunction "P14.8_37") (pintype "bidirectional"))
      (node (ref "R19") (pin "1") (pinfunction "1_1") (pintype "passive"))
      (node (ref "R28") (pin "2") (pinfunction "2_2") (pintype "passive"))
    )
    (net (code "68") (name "/P14.9") (class "Default")
      (node (ref "IC1") (pin "36") (pinfunction "P14.9_36") (pintype "bidirectional"))
    )
    (net (code "69") (name "/P14.12") (class "Default")
      (node (ref "IC1") (pin "23") (pinfunction "P14.12_23") (pintype "bidirectional"))
    )
    (net (code "70") (name "/P14.13") (class "Default")
      (node (ref "IC1") (pin "22") (pinfunction "P14.13_22") (pintype "bidirectional"))
    )
    (net (code "71") (name "/P14.14") (class "Default")
      (node (ref "IC1") (pin "21") (pinfunction "P14.14_21") (pintype "bidirectional"))
    )
    (net (code "72") (name "/P14.15") (class "Default")
      (node (ref "IC1") (pin "20") (pinfunction "P14.15_20") (pintype "bidirectional"))
    )
    (net (code "73") (name "/P15.2") (class "Default")
      (node (ref "IC1") (pin "19") (pinfunction "P15.2_19") (pintype "bidirectional"))
    )
    (net (code "74") (name "/P15.3") (class "Default")
      (node (ref "IC1") (pin "18") (pinfunction "P15.3_18") (pintype "bidirectional"))
    )
    (net (code "75") (name "/P15.8") (class "Default")
      (node (ref "IC1") (pin "39") (pinfunction "P15.8_39") (pintype "bidirectional"))
    )
    (net (code "76") (name "/P15.9") (class "Default")
      (node (ref "IC1") (pin "38") (pinfunction "P15.9_38") (pintype "bidirectional"))
    )
    (net (code "77") (name "/RESET#") (class "Default")
      (node (ref "C20") (pin "1") (pinfunction "1_1") (pintype "passive"))
      (node (ref "CON1") (pin "4") (pinfunction "4_4") (pintype "passive"))
      (node (ref "IC1") (pin "65") (pinfunction "PORST#_65") (pintype "bidirectional"))
      (node (ref "R1") (pin "1") (pinfunction "1_1") (pintype "passive"))
      (node (ref "SW3") (pin "P") (pinfunction "P_P") (pintype "passive"))
      (node (ref "SW3") (pin "P1") (pinfunction "P_P1") (pintype "passive"))
      (node (ref "V1") (pin "2") (pinfunction "A_2") (pintype "passive"))
    )
    (net (code "78") (name "/RTC1") (class "Default")
      (node (ref "IC1") (pin "15") (pinfunction "RTC_XTAL_1_15") (pintype "bidirectional"))
    )
    (net (code "79") (name "/RTC2") (class "Default")
      (node (ref "IC1") (pin "16") (pinfunction "RTC_XTAL_2_16") (pintype "bidirectional"))
    )
    (net (code "80") (name "/TCK") (class "Default")
      (node (ref "CON1") (pin "3") (pinfunction "3_3") (pintype "passive"))
      (node (ref "IC1") (pin "67") (pinfunction "TCK_67") (pintype "bidirectional"))
      (node (ref "X1") (pin "4") (pinfunction "4_4") (pintype "passive"))
    )
    (net (code "81") (name "/TMS") (class "Default")
      (node (ref "CON1") (pin "1") (pinfunction "1_1") (pintype "passive"))
      (node (ref "IC1") (pin "66") (pinfunction "TMS_66") (pintype "bidirectional"))
      (node (ref "X1") (pin "2") (pinfunction "2_2") (pintype "passive"))
    )
    (net (code "82") (name "/USB_D+") (class "Default")
      (node (ref "IC1") (pin "9") (pinfunction "USB_D+_9") (pintype "bidirectional"))
      (node (ref "R11") (pin "2") (pinfunction "2_2") (pintype "passive"))
    )
    (net (code "83") (name "/USB_D-") (class "Default")
      (node (ref "IC1") (pin "8") (pinfunction "USB_D-_8") (pintype "bidirectional"))
      (node (ref "R10") (pin "2") (pinfunction "2_2") (pintype "passive"))
    )
    (net (code "84") (name "/VAREF") (class "Default")
      (node (ref "C16") (pin "1") (pinfunction "1_1") (pintype "passive"))
      (node (ref "IC1") (pin "33") (pinfunction "VAREF_33") (pintype "bidirectional"))
      (node (ref "L2") (pin "1") (pinfunction "1_1") (pintype "passive"))
    )
    (net (code "85") (name "/VBAT_IN") (class "Default")
      (node (ref "47µH") (pin "P$2") (pinfunction "2_P$2") (pintype "bidirectional"))
      (node (ref "BAT_IN") (pin "2") (pinfunction "2_2") (pintype "passive"))
      (node (ref "BAT_IN") (pin "4") (pinfunction "4_4") (pintype "passive"))
      (node (ref "C25") (pin "1") (pinfunction "1_1") (pintype "passive"))
      (node (ref "C27") (pin "1") (pinfunction "1_1") (pintype "passive"))
      (node (ref "C32") (pin "1") (pinfunction "1_1") (pintype "passive"))
      (node (ref "C33") (pin "2") (pinfunction "2_2") (pintype "passive"))
      (node (ref "JP10") (pin "1") (pinfunction "1_1") (pintype "passive"))
      (node (ref "JP11") (pin "1") (pinfunction "1_1") (pintype "passive"))
      (node (ref "M1/MOTOR") (pin "10") (pinfunction "10_10") (pintype "passive"))
      (node (ref "M1/MOTOR") (pin "9") (pinfunction "9_9") (pintype "passive"))
      (node (ref "M2/MOTOR") (pin "10") (pinfunction "10_10") (pintype "passive"))
      (node (ref "M2/MOTOR") (pin "9") (pinfunction "9_9") (pintype "passive"))
      (node (ref "M3/MOTOR") (pin "10") (pinfunction "10_10") (pintype "passive"))
      (node (ref "M3/MOTOR") (pin "9") (pinfunction "9_9") (pintype "passive"))
      (node (ref "M4/MOTOR") (pin "10") (pinfunction "10_10") (pintype "passive"))
      (node (ref "M4/MOTOR") (pin "9") (pinfunction "9_9") (pintype "passive"))
      (node (ref "U$12") (pin "P$1") (pinfunction "P$1_P$1") (pintype "bidirectional"))
      (node (ref "U$7") (pin "7") (pinfunction "7_7") (pintype "bidirectional"))
    )
    (net (code "86") (name "/VBUS") (class "Default")
      (node (ref "D2") (pin "A") (pinfunction "A_A") (pintype "passive"))
      (node (ref "IC1") (pin "10") (pinfunction "VBUS_10") (pintype "bidirectional"))
      (node (ref "L1") (pin "1") (pinfunction "1_1") (pintype "passive"))
    )
    (net (code "87") (name "/VDDA") (class "Default")
      (node (ref "C17") (pin "1") (pinfunction "1_1") (pintype "passive"))
      (node (ref "IC1") (pin "35") (pinfunction "VDDA_35") (pintype "bidirectional"))
      (node (ref "L3") (pin "1") (pinfunction "1_1") (pintype "passive"))
    )
    (net (code "88") (name "/VDDC") (class "Default")
      (node (ref "C10") (pin "1") (pinfunction "1_1") (pintype "passive"))
      (node (ref "C11") (pin "1") (pinfunction "1_1") (pintype "passive"))
      (node (ref "C7") (pin "1") (pinfunction "1_1") (pintype "passive"))
      (node (ref "C8") (pin "1") (pinfunction "1_1") (pintype "passive"))
      (node (ref "C9") (pin "1") (pinfunction "1_1") (pintype "passive"))
      (node (ref "IC1") (pin "12") (pinfunction "VDDC_12") (pintype "bidirectional"))
      (node (ref "IC1") (pin "42") (pinfunction "VDDC1_42") (pintype "bidirectional"))
      (node (ref "IC1") (pin "64") (pinfunction "VDDC2_64") (pintype "bidirectional"))
      (node (ref "IC1") (pin "86") (pinfunction "VDDC3_86") (pintype "bidirectional"))
    )
    (net (code "89") (name "AGND") (class "Default")
      (node (ref "C16") (pin "2") (pinfunction "2_2") (pintype "passive"))
      (node (ref "C17") (pin "2") (pinfunction "2_2") (pintype "passive"))
      (node (ref "IC1") (pin "32") (pinfunction "VAGND_32") (pintype "bidirectional"))
      (node (ref "IC1") (pin "34") (pinfunction "VSSA_34") (pintype "bidirectional"))
    )
    (net (code "90") (name "GND") (class "Default")
      (node (ref "BAT_IN") (pin "1") (pinfunction "1_1") (pintype "passive"))
      (node (ref "BAT_IN") (pin "3") (pinfunction "3_3") (pintype "passive"))
      (node (ref "C1") (pin "2") (pinfunction "2_2") (pintype "passive"))
      (node (ref "C10") (pin "2") (pinfunction "2_2") (pintype "passive"))
      (node (ref "C11") (pin "2") (pinfunction "2_2") (pintype "passive"))
      (node (ref "C12") (pin "2") (pinfunction "2_2") (pintype "passive"))
      (node (ref "C13") (pin "2") (pinfunction "2_2") (pintype "passive"))
      (node (ref "C14") (pin "2") (pinfunction "2_2") (pintype "passive"))
      (node (ref "C15") (pin "1") (pinfunction "1_1") (pintype "passive"))
      (node (ref "C18") (pin "1") (pinfunction "1_1") (pintype "passive"))
      (node (ref "C19") (pin "1") (pinfunction "1_1") (pintype "passive"))
      (node (ref "C2") (pin "2") (pinfunction "2_2") (pintype "passive"))
      (node (ref "C20") (pin "2") (pinfunction "2_2") (pintype "passive"))
      (node (ref "C21") (pin "1") (pinfunction "1_1") (pintype "passive"))
      (node (ref "C22") (pin "2") (pinfunction "2_2") (pintype "passive"))
      (node (ref "C23") (pin "2") (pinfunction "2_2") (pintype "passive"))
      (node (ref "C24") (pin "1") (pinfunction "1_1") (pintype "passive"))
      (node (ref "C25") (pin "2") (pinfunction "2_2") (pintype "passive"))
      (node (ref "C26") (pin "2") (pinfunction "2_2") (pintype "passive"))
      (node (ref "C27") (pin "2") (pinfunction "2_2") (pintype "passive"))
      (node (ref "C28") (pin "1") (pinfunction "1_1") (pintype "passive"))
      (node (ref "C29") (pin "2") (pinfunction "2_2") (pintype "passive"))
      (node (ref "C3") (pin "2") (pinfunction "2_2") (pintype "passive"))
      (node (ref "C30") (pin "2") (pinfunction "2_2") (pintype "passive"))
      (node (ref "C31") (pin "2") (pinfunction "2_2") (pintype "passive"))
      (node (ref "C32") (pin "2") (pinfunction "2_2") (pintype "passive"))
      (node (ref "C33") (pin "1") (pinfunction "1_1") (pintype "passive"))
      (node (ref "C35") (pin "2") (pinfunction "2_2") (pintype "passive"))
      (node (ref "C37") (pin "2") (pinfunction "2_2") (pintype "passive"))
      (node (ref "C38") (pin "2") (pinfunction "2_2") (pintype "passive"))
      (node (ref "C4") (pin "2") (pinfunction "2_2") (pintype "passive"))
      (node (ref "C5") (pin "2") (pinfunction "2_2") (pintype "passive"))
      (node (ref "C6") (pin "2") (pinfunction "2_2") (pintype "passive"))
      (node (ref "C7") (pin "2") (pinfunction "2_2") (pintype "passive"))
      (node (ref "C8") (pin "2") (pinfunction "2_2") (pintype "passive"))
      (node (ref "C9") (pin "2") (pinfunction "2_2") (pintype "passive"))
      (node (ref "CON1") (pin "6") (pinfunction "6_6") (pintype "passive"))
      (node (ref "D1") (pin "3") (pinfunction "3_3") (pintype "passive"))
      (node (ref "IC1") (pin "59") (pinfunction "VSS_59") (pintype "bidirectional"))
      (node (ref "IC1") (pin "63") (pinfunction "VSSO_63") (pintype "bidirectional"))
      (node (ref "IC1") (pin "EXP") (pinfunction "EPAD_EXP") (pintype "bidirectional"))
      (node (ref "IC2") (pin "18") (pinfunction "18_18") (pintype "bidirectional"))
      (node (ref "IC2") (pin "20") (pinfunction "20_20") (pintype "bidirectional"))
      (node (ref "JP1") (pin "2") (pinfunction "2_2") (pintype "passive"))
      (node (ref "JP2") (pin "1") (pinfunction "1_1") (pintype "passive"))
      (node (ref "JP24") (pin "1") (pinfunction "1_1") (pintype "passive"))
      (node (ref "JP5") (pin "2") (pinfunction "2_2") (pintype "passive"))
      (node (ref "JP6") (pin "2") (pinfunction "2_2") (pintype "passive"))
      (node (ref "LED1") (pin "C") (pinfunction "C_C") (pintype "passive"))
      (node (ref "LED2") (pin "C") (pinfunction "C_C") (pintype "passive"))
      (node (ref "LED3") (pin "C") (pinfunction "C_C") (pintype "passive"))
      (node (ref "LED4") (pin "C") (pinfunction "C_C") (pintype "passive"))
      (node (ref "LED5") (pin "C") (pinfunction "C_C") (pintype "passive"))
      (node (ref "LED6") (pin "C") (pinfunction "C_C") (pintype "passive"))
      (node (ref "M1/DY") (pin "1") (pinfunction "1_1") (pintype "passive"))
      (node (ref "M1/DY") (pin "2") (pinfunction "2_2") (pintype "passive"))
      (node (ref "M1/MOTOR") (pin "7") (pinfunction "7_7") (pintype "passive"))
      (node (ref "M1/MOTOR") (pin "8") (pinfunction "8_8") (pintype "passive"))
      (node (ref "M2/DY") (pin "1") (pinfunction "1_1") (pintype "passive"))
      (node (ref "M2/DY") (pin "2") (pinfunction "2_2") (pintype "passive"))
      (node (ref "M2/MOTOR") (pin "7") (pinfunction "7_7") (pintype "passive"))
      (node (ref "M2/MOTOR") (pin "8") (pinfunction "8_8") (pintype "passive"))
      (node (ref "M3/DY") (pin "1") (pinfunction "1_1") (pintype "passive"))
      (node (ref "M3/DY") (pin "2") (pinfunction "2_2") (pintype "passive"))
      (node (ref "M3/MOTOR") (pin "7") (pinfunction "7_7") (pintype "passive"))
      (node (ref "M3/MOTOR") (pin "8") (pinfunction "8_8") (pintype "passive"))
      (node (ref "M4/DY") (pin "1") (pinfunction "1_1") (pintype "passive"))
      (node (ref "M4/DY") (pin "2") (pinfunction "2_2") (pintype "passive"))
      (node (ref "M4/MOTOR") (pin "7") (pinfunction "7_7") (pintype "passive"))
      (node (ref "M4/MOTOR") (pin "8") (pinfunction "8_8") (pintype "passive"))
      (node (ref "R18") (pin "2") (pinfunction "2_2") (pintype "passive"))
      (node (ref "R19") (pin "2") (pinfunction "2_2") (pintype "passive"))
      (node (ref "R24") (pin "2") (pinfunction "2_2") (pintype "passive"))
      (node (ref "R26") (pin "2") (pinfunction "2_2") (pintype "passive"))
      (node (ref "R27") (pin "2") (pinfunction "2_2") (pintype "passive"))
      (node (ref "R30") (pin "2") (pinfunction "2_2") (pintype "passive"))
      (node (ref "R7") (pin "2") (pinfunction "2_2") (pintype "passive"))
      (node (ref "RC") (pin "2") (pinfunction "2_2") (pintype "passive"))
      (node (ref "SW3") (pin "S") (pinfunction "S_S") (pintype "passive"))
      (node (ref "SW3") (pin "S1") (pinfunction "S_S1") (pintype "passive"))
      (node (ref "TO3.3V") (pin "1") (pinfunction "ADJ_1") (pintype "power_in"))
      (node (ref "U$11") (pin "A1") (pinfunction "A1/VSS_A1") (pintype "bidirectional"))
      (node (ref "U$11") (pin "A2") (pinfunction "A2/VSS_A2") (pintype "bidirectional"))
      (node (ref "U$11") (pin "C1") (pinfunction "C1/VSS_C1") (pintype "bidirectional"))
      (node (ref "U$13") (pin "GND1") (pinfunction "1_GND_GND1") (pintype "bidirectional"))
      (node (ref "U$13") (pin "GND2") (pinfunction "12_GND_GND2") (pintype "bidirectional"))
      (node (ref "U$13") (pin "GND3") (pinfunction "29_GND_GND3") (pintype "bidirectional"))
      (node (ref "U$13") (pin "GND4") (pinfunction "28_GND_GND4") (pintype "bidirectional"))
      (node (ref "U$14") (pin "P$1") (pinfunction "P$1_P$1") (pintype "bidirectional"))
      (node (ref "U$16") (pin "1") (pinfunction "1_1") (pintype "bidirectional"))
      (node (ref "U$18") (pin "P_4") (pinfunction "P4/GND_P_4") (pintype "bidirectional"))
      (node (ref "U$20") (pin "P_4") (pinfunction "P4/GND_P_4") (pintype "bidirectional"))
      (node (ref "U$22") (pin "P$1") (pinfunction "P$1_P$1") (pintype "bidirectional"))
      (node (ref "U$7") (pin "1") (pinfunction "1_1") (pintype "bidirectional"))
      (node (ref "U$7") (pin "2") (pinfunction "2_2") (pintype "bidirectional"))
      (node (ref "U$8") (pin "P1") (pinfunction "GND1_P1") (pintype "bidirectional"))
      (node (ref "U$8") (pin "P7") (pinfunction "GND2_P7") (pintype "bidirectional"))
      (node (ref "U$9") (pin "P$1") (pinfunction "P$1_P$1") (pintype "bidirectional"))
      (node (ref "USB") (pin "5") (pinfunction "5_5") (pintype "passive"))
      (node (ref "X1") (pin "3") (pinfunction "3_3") (pintype "passive"))
      (node (ref "X1") (pin "5") (pinfunction "5_5") (pintype "passive"))
    )
    (net (code "91") (name "Net-(47UH-1)") (class "Default")
      (node (ref "47UH") (pin "P$1") (pinfunction "1_P$1") (pintype "bidirectional"))
      (node (ref "C34") (pin "1") (pinfunction "1_1") (pintype "passive"))
      (node (ref "U$16") (pin "2") (pinfunction "2_2") (pintype "bidirectional"))
      (node (ref "U$7") (pin "6") (pinfunction "6_6") (pintype "bidirectional"))
    )
    (net (code "92") (name "Net-(47µH-1)") (class "Default")
      (node (ref "47µH") (pin "P$1") (pinfunction "1_P$1") (pintype "bidirectional"))
      (node (ref "C24") (pin "2") (pinfunction "2_2") (pintype "passive"))
      (node (ref "U$7") (pin "8") (pinfunction "8_8") (pintype "bidirectional"))
    )
    (net (code "93") (name "Net-(C19-Pad2)") (class "Default")
      (node (ref "C19") (pin "2") (pinfunction "2_2") (pintype "passive"))
      (node (ref "IC2") (pin "10") (pinfunction "10_10") (pintype "bidirectional"))
    )
    (net (code "94") (name "Net-(C34-Pad2)") (class "Default")
      (node (ref "C34") (pin "2") (pinfunction "2_2") (pintype "passive"))
      (node (ref "U$7") (pin "5") (pinfunction "5_5") (pintype "bidirectional"))
    )
    (net (code "95") (name "Net-(C36-Pad1)") (class "Default")
      (node (ref "C36") (pin "1") (pinfunction "1_1") (pintype "passive"))
      (node (ref "U$7") (pin "3") (pinfunction "3_3") (pintype "bidirectional"))
    )
    (net (code "96") (name "Net-(C36-Pad2)") (class "Default")
      (node (ref "C36") (pin "2") (pinfunction "2_2") (pintype "passive"))
      (node (ref "R24") (pin "1") (pinfunction "1_1") (pintype "passive"))
    )
    (net (code "97") (name "Net-(D1-Pad2)") (class "Default")
      (node (ref "D1") (pin "2") (pinfunction "2_2") (pintype "passive"))
      (node (ref "R10") (pin "1") (pinfunction "1_1") (pintype "passive"))
      (node (ref "USB") (pin "2") (pinfunction "2_2") (pintype "passive"))
    )
    (net (code "98") (name "Net-(IC1-XTAL1)") (class "Default")
      (node (ref "C12") (pin "1") (pinfunction "1_1") (pintype "passive"))
      (node (ref "IC1") (pin "61") (pinfunction "XTAL1_61") (pintype "bidirectional"))
      (node (ref "Q1") (pin "1") (pinfunction "1_1") (pintype "passive"))
    )
    (net (code "99") (name "Net-(IC1-XTAL2)") (class "Default")
      (node (ref "IC1") (pin "62") (pinfunction "XTAL2_62") (pintype "bidirectional"))
      (node (ref "R12") (pin "1") (pinfunction "1_1") (pintype "passive"))
    )
    (net (code "100") (name "Net-(JP4-Pad1)") (class "Default")
      (node (ref "JP4") (pin "1") (pinfunction "1_1") (pintype "passive"))
      (node (ref "R3") (pin "2") (pinfunction "2_2") (pintype "passive"))
      (node (ref "R4") (pin "2") (pinfunction "2_2") (pintype "passive"))
      (node (ref "R7") (pin "1") (pinfunction "1_1") (pintype "passive"))
      (node (ref "U$22") (pin "P$2") (pinfunction "P$2_P$2") (pintype "bidirectional"))
    )
    (net (code "101") (name "Net-(JP15-Pad1)") (class "Default")
      (node (ref "JP15") (pin "1") (pinfunction "1_1") (pintype "passive"))
      (node (ref "M1/MOTOR") (pin "5") (pinfunction "5_5") (pintype "passive"))
      (node (ref "M1/MOTOR") (pin "6") (pinfunction "6_6") (pintype "passive"))
    )
    (net (code "102") (name "Net-(JP15-Pad2)") (class "Default")
      (node (ref "JP15") (pin "2") (pinfunction "2_2") (pintype "passive"))
      (node (ref "M1/MOTOR") (pin "3") (pinfunction "3_3") (pintype "passive"))
      (node (ref "M1/MOTOR") (pin "4") (pinfunction "4_4") (pintype "passive"))
    )
    (net (code "103") (name "Net-(JP15-Pad3)") (class "Default")
      (node (ref "JP15") (pin "3") (pinfunction "3_3") (pintype "passive"))
      (node (ref "M1/MOTOR") (pin "1") (pinfunction "1_1") (pintype "passive"))
      (node (ref "M1/MOTOR") (pin "2") (pinfunction "2_2") (pintype "passive"))
    )
    (net (code "104") (name "Net-(JP16-Pad1)") (class "Default")
      (node (ref "JP16") (pin "1") (pinfunction "1_1") (pintype "passive"))
      (node (ref "M2/MOTOR") (pin "5") (pinfunction "5_5") (pintype "passive"))
      (node (ref "M2/MOTOR") (pin "6") (pinfunction "6_6") (pintype "passive"))
    )
    (net (code "105") (name "Net-(JP16-Pad2)") (class "Default")
      (node (ref "JP16") (pin "2") (pinfunction "2_2") (pintype "passive"))
      (node (ref "M2/MOTOR") (pin "3") (pinfunction "3_3") (pintype "passive"))
      (node (ref "M2/MOTOR") (pin "4") (pinfunction "4_4") (pintype "passive"))
    )
    (net (code "106") (name "Net-(JP16-Pad3)") (class "Default")
      (node (ref "JP16") (pin "3") (pinfunction "3_3") (pintype "passive"))
      (node (ref "M2/MOTOR") (pin "1") (pinfunction "1_1") (pintype "passive"))
      (node (ref "M2/MOTOR") (pin "2") (pinfunction "2_2") (pintype "passive"))
    )
    (net (code "107") (name "Net-(JP17-Pad1)") (class "Default")
      (node (ref "JP17") (pin "1") (pinfunction "1_1") (pintype "passive"))
      (node (ref "M3/MOTOR") (pin "5") (pinfunction "5_5") (pintype "passive"))
      (node (ref "M3/MOTOR") (pin "6") (pinfunction "6_6") (pintype "passive"))
    )
    (net (code "108") (name "Net-(JP17-Pad2)") (class "Default")
      (node (ref "JP17") (pin "2") (pinfunction "2_2") (pintype "passive"))
      (node (ref "M3/MOTOR") (pin "3") (pinfunction "3_3") (pintype "passive"))
      (node (ref "M3/MOTOR") (pin "4") (pinfunction "4_4") (pintype "passive"))
    )
    (net (code "109") (name "Net-(JP17-Pad3)") (class "Default")
      (node (ref "JP17") (pin "3") (pinfunction "3_3") (pintype "passive"))
      (node (ref "M3/MOTOR") (pin "1") (pinfunction "1_1") (pintype "passive"))
      (node (ref "M3/MOTOR") (pin "2") (pinfunction "2_2") (pintype "passive"))
    )
    (net (code "110") (name "Net-(JP18-Pad1)") (class "Default")
      (node (ref "JP18") (pin "1") (pinfunction "1_1") (pintype "passive"))
      (node (ref "M4/MOTOR") (pin "5") (pinfunction "5_5") (pintype "passive"))
      (node (ref "M4/MOTOR") (pin "6") (pinfunction "6_6") (pintype "passive"))
    )
    (net (code "111") (name "Net-(JP18-Pad2)") (class "Default")
      (node (ref "JP18") (pin "2") (pinfunction "2_2") (pintype "passive"))
      (node (ref "M4/MOTOR") (pin "3") (pinfunction "3_3") (pintype "passive"))
      (node (ref "M4/MOTOR") (pin "4") (pinfunction "4_4") (pintype "passive"))
    )
    (net (code "112") (name "Net-(JP18-Pad3)") (class "Default")
      (node (ref "JP18") (pin "3") (pinfunction "3_3") (pintype "passive"))
      (node (ref "M4/MOTOR") (pin "1") (pinfunction "1_1") (pintype "passive"))
      (node (ref "M4/MOTOR") (pin "2") (pinfunction "2_2") (pintype "passive"))
    )
    (net (code "113") (name "Net-(JP19-Pad1)") (class "Default")
      (node (ref "JP19") (pin "1") (pinfunction "1_1") (pintype "passive"))
      (node (ref "R13") (pin "1") (pinfunction "1_1") (pintype "passive"))
    )
    (net (code "114") (name "Net-(JP19-Pad2)") (class "Default")
      (node (ref "JP19") (pin "2") (pinfunction "2_2") (pintype "passive"))
      (node (ref "R28") (pin "1") (pinfunction "1_1") (pintype "passive"))
    )
    (net (code "115") (name "Net-(JP19-Pad3)") (class "Default")
      (node (ref "JP19") (pin "3") (pinfunction "3_3") (pintype "passive"))
      (node (ref "R29") (pin "1") (pinfunction "1_1") (pintype "passive"))
    )
    (net (code "116") (name "Net-(L1-Pad2)") (class "Default")
      (node (ref "L1") (pin "2") (pinfunction "2_2") (pintype "passive"))
      (node (ref "USB") (pin "1") (pinfunction "1_1") (pintype "passive"))
    )
    (net (code "117") (name "Net-(LED1-PadA)") (class "Default")
      (node (ref "LED1") (pin "A") (pinfunction "A_A") (pintype "passive"))
      (node (ref "R6") (pin "1") (pinfunction "1_1") (pintype "passive"))
    )
    (net (code "118") (name "Net-(LED2-PadA)") (class "Default")
      (node (ref "LED2") (pin "A") (pinfunction "A_A") (pintype "passive"))
      (node (ref "R20") (pin "1") (pinfunction "1_1") (pintype "passive"))
    )
    (net (code "119") (name "Net-(LED3-PadA)") (class "Default")
      (node (ref "LED3") (pin "A") (pinfunction "A_A") (pintype "passive"))
      (node (ref "R21") (pin "1") (pinfunction "1_1") (pintype "passive"))
    )
    (net (code "120") (name "Net-(LED4-PadA)") (class "Default")
      (node (ref "LED4") (pin "A") (pinfunction "A_A") (pintype "passive"))
      (node (ref "R22") (pin "1") (pinfunction "1_1") (pintype "passive"))
    )
    (net (code "121") (name "Net-(LED5-PadA)") (class "Default")
      (node (ref "LED5") (pin "A") (pinfunction "A_A") (pintype "passive"))
      (node (ref "R23") (pin "1") (pinfunction "1_1") (pintype "passive"))
    )
    (net (code "122") (name "Net-(LED6-PadA)") (class "Default")
      (node (ref "LED6") (pin "A") (pinfunction "A_A") (pintype "passive"))
      (node (ref "R5") (pin "1") (pinfunction "1_1") (pintype "passive"))
    )
    (net (code "123") (name "Net-(M1/DY-Pad6)") (class "Default")
      (node (ref "M1/DY") (pin "6") (pinfunction "6_6") (pintype "passive"))
      (node (ref "M2/DY") (pin "5") (pinfunction "5_5") (pintype "passive"))
      (node (ref "R35") (pin "1") (pinfunction "1_1") (pintype "passive"))
    )
    (net (code "124") (name "Net-(M2/DY-Pad6)") (class "Default")
      (node (ref "M2/DY") (pin "6") (pinfunction "6_6") (pintype "passive"))
      (node (ref "M3/DY") (pin "5") (pinfunction "5_5") (pintype "passive"))
      (node (ref "R37") (pin "1") (pinfunction "1_1") (pintype "passive"))
    )
    (net (code "125") (name "Net-(M3/DY-Pad6)") (class "Default")
      (node (ref "M3/DY") (pin "6") (pinfunction "6_6") (pintype "passive"))
      (node (ref "M4/DY") (pin "5") (pinfunction "5_5") (pintype "passive"))
      (node (ref "R38") (pin "1") (pinfunction "1_1") (pintype "passive"))
    )
    (net (code "126") (name "Net-(Q1-2)") (class "Default")
      (node (ref "C13") (pin "1") (pinfunction "1_1") (pintype "passive"))
      (node (ref "Q1") (pin "3") (pinfunction "2_3") (pintype "passive"))
      (node (ref "R12") (pin "2") (pinfunction "2_2") (pintype "passive"))
    )
    (net (code "127") (name "Net-(R2-Pad1)") (class "Default")
      (node (ref "R2") (pin "1") (pinfunction "1_1") (pintype "passive"))
      (node (ref "SJ1") (pin "1") (pinfunction "1_1") (pintype "passive"))
      (node (ref "U$9") (pin "P$2") (pinfunction "P$2_P$2") (pintype "bidirectional"))
    )
    (net (code "128") (name "Net-(U$11-B2{slash}VDD)") (class "Default")
      (node (ref "C28") (pin "2") (pinfunction "2_2") (pintype "passive"))
      (node (ref "R2") (pin "2") (pinfunction "2_2") (pintype "passive"))
      (node (ref "U$11") (pin "B2") (pinfunction "B2/VDD_B2") (pintype "bidirectional"))
    )
    (net (code "129") (name "Net-(U$11-C2{slash}BIF)") (class "Default")
      (node (ref "R3") (pin "1") (pinfunction "1_1") (pintype "passive"))
      (node (ref "U$11") (pin "C2") (pinfunction "C2/BIF_C2") (pintype "bidirectional"))
    )
    (net (code "130") (name "Net-(U$13-13_RX)") (class "Default")
      (node (ref "JP2") (pin "4") (pinfunction "4_4") (pintype "passive"))
      (node (ref "SJ3") (pin "2") (pinfunction "2_2") (pintype "passive"))
      (node (ref "U$13") (pin "UART_RX") (pinfunction "13_RX_UART_RX") (pintype "bidirectional"))
    )
    (net (code "131") (name "Net-(U$13-14_TX)") (class "Default")
      (node (ref "JP2") (pin "2") (pinfunction "2_2") (pintype "passive"))
      (node (ref "SJ2") (pin "2") (pinfunction "2_2") (pintype "passive"))
      (node (ref "U$13") (pin "UART_TX") (pinfunction "14_TX_UART_TX") (pintype "bidirectional"))
    )
    (net (code "132") (name "Net-(U$13-15_RTS)") (class "Default")
      (node (ref "U$13") (pin "UART_CTX") (pinfunction "16_CTS_UART_CTX") (pintype "bidirectional"))
      (node (ref "U$13") (pin "UART_RTX") (pinfunction "15_RTS_UART_RTX") (pintype "bidirectional"))
    )
    (net (code "133") (name "Net-(U$13-19_LED)") (class "Default")
      (node (ref "R6") (pin "2") (pinfunction "2_2") (pintype "passive"))
      (node (ref "U$13") (pin "GPIO_2") (pinfunction "19_LED_GPIO_2") (pintype "bidirectional"))
    )
    (net (code "134") (name "Net-(U$18-P2{slash}OUT)") (class "Default")
      (node (ref "JP10") (pin "2") (pinfunction "2_2") (pintype "passive"))
      (node (ref "U$18") (pin "P_2") (pinfunction "P2/OUT_P_2") (pintype "bidirectional"))
      (node (ref "U$18") (pin "P_3") (pinfunction "P3/OUT_P_3") (pintype "bidirectional"))
      (node (ref "U$18") (pin "P_5") (pinfunction "P5/OUT_P_5") (pintype "bidirectional"))
    )
    (net (code "135") (name "Net-(U$18-P6{slash}REXT)") (class "Default")
      (node (ref "R26") (pin "1") (pinfunction "1_1") (pintype "passive"))
      (node (ref "U$18") (pin "P_6") (pinfunction "P6/REXT_P_6") (pintype "bidirectional"))
    )
    (net (code "136") (name "Net-(U$20-P2{slash}OUT)") (class "Default")
      (node (ref "JP11") (pin "2") (pinfunction "2_2") (pintype "passive"))
      (node (ref "U$20") (pin "P_2") (pinfunction "P2/OUT_P_2") (pintype "bidirectional"))
      (node (ref "U$20") (pin "P_3") (pinfunction "P3/OUT_P_3") (pintype "bidirectional"))
      (node (ref "U$20") (pin "P_5") (pinfunction "P5/OUT_P_5") (pintype "bidirectional"))
    )
    (net (code "137") (name "Net-(U$20-P6{slash}REXT)") (class "Default")
      (node (ref "R27") (pin "1") (pinfunction "1_1") (pintype "passive"))
      (node (ref "U$20") (pin "P_6") (pinfunction "P6/REXT_P_6") (pintype "bidirectional"))
    )
    (net (code "138") (name "Net-(USB-3)") (class "Default")
      (node (ref "D1") (pin "1") (pinfunction "1_1") (pintype "passive"))
      (node (ref "R11") (pin "1") (pinfunction "1_1") (pintype "passive"))
      (node (ref "USB") (pin "3+") (pinfunction "3_3+") (pintype "passive"))
    )
    (net (code "139") (name "Net-(V1-C)") (class "Default")
      (node (ref "V1") (pin "1") (pinfunction "C_1") (pintype "passive"))
      (node (ref "X1") (pin "10") (pinfunction "10_10") (pintype "passive"))
    )
    (net (code "140") (name "VDD3.3") (class "Default")
      (node (ref "C1") (pin "1") (pinfunction "1_1") (pintype "passive"))
      (node (ref "C14") (pin "1") (pinfunction "1_1") (pintype "passive"))
      (node (ref "C15") (pin "2") (pinfunction "2_2") (pintype "passive"))
      (node (ref "C18") (pin "2") (pinfunction "2_2") (pintype "passive"))
      (node (ref "C2") (pin "1") (pinfunction "1_1") (pintype "passive"))
      (node (ref "C21") (pin "2") (pinfunction "2_2") (pintype "passive"))
      (node (ref "C23") (pin "1") (pinfunction "1_1") (pintype "passive"))
      (node (ref "C3") (pin "1") (pinfunction "1_1") (pintype "passive"))
      (node (ref "C37") (pin "1") (pinfunction "1_1") (pintype "passive"))
      (node (ref "C38") (pin "1") (pinfunction "1_1") (pintype "passive"))
      (node (ref "C4") (pin "1") (pinfunction "1_1") (pintype "passive"))
      (node (ref "C5") (pin "1") (pinfunction "1_1") (pintype "passive"))
      (node (ref "C6") (pin "1") (pinfunction "1_1") (pintype "passive"))
      (node (ref "CON1") (pin "2") (pinfunction "2_2") (pintype "passive"))
      (node (ref "IC1") (pin "11") (pinfunction "VDDP_11") (pintype "bidirectional"))
      (node (ref "IC1") (pin "17") (pinfunction "VBAT_17") (pintype "bidirectional"))
      (node (ref "IC1") (pin "43") (pinfunction "VDDP1_43") (pintype "bidirectional"))
      (node (ref "IC1") (pin "60") (pinfunction "VDDP2_60") (pintype "bidirectional"))
      (node (ref "IC1") (pin "87") (pinfunction "VDDP3_87") (pintype "bidirectional"))
      (node (ref "IC2") (pin "13") (pinfunction "13_13") (pintype "bidirectional"))
      (node (ref "IC2") (pin "22") (pinfunction "22_22") (pintype "bidirectional"))
      (node (ref "IC2") (pin "8") (pinfunction "8_8") (pintype "bidirectional"))
      (node (ref "JP1") (pin "1") (pinfunction "1_1") (pintype "passive"))
      (node (ref "JP2") (pin "3") (pinfunction "3_3") (pintype "passive"))
      (node (ref "JP24") (pin "2") (pinfunction "2_2") (pintype "passive"))
      (node (ref "JP6") (pin "1") (pinfunction "1_1") (pintype "passive"))
      (node (ref "L2") (pin "2") (pinfunction "2_2") (pintype "passive"))
      (node (ref "L3") (pin "2") (pinfunction "2_2") (pintype "passive"))
      (node (ref "M1/DY") (pin "3") (pinfunction "3_3") (pintype "passive"))
      (node (ref "M1/DY") (pin "4") (pinfunction "4_4") (pintype "passive"))
      (node (ref "M2/DY") (pin "3") (pinfunction "3_3") (pintype "passive"))
      (node (ref "M2/DY") (pin "4") (pinfunction "4_4") (pintype "passive"))
      (node (ref "M3/DY") (pin "3") (pinfunction "3_3") (pintype "passive"))
      (node (ref "M3/DY") (pin "4") (pinfunction "4_4") (pintype "passive"))
      (node (ref "M4/DY") (pin "3") (pinfunction "3_3") (pintype "passive"))
      (node (ref "M4/DY") (pin "4") (pinfunction "4_4") (pintype "passive"))
      (node (ref "R1") (pin "2") (pinfunction "2_2") (pintype "passive"))
      (node (ref "R14") (pin "2") (pinfunction "2_2") (pintype "passive"))
      (node (ref "R15") (pin "2") (pinfunction "2_2") (pintype "passive"))
      (node (ref "R16") (pin "1") (pinfunction "1_1") (pintype "passive"))
      (node (ref "R17") (pin "1") (pinfunction "1_1") (pintype "passive"))
      (node (ref "R4") (pin "1") (pinfunction "1_1") (pintype "passive"))
      (node (ref "R5") (pin "2") (pinfunction "2_2") (pintype "passive"))
      (node (ref "R8") (pin "1") (pinfunction "1_1") (pintype "passive"))
      (node (ref "R9") (pin "1") (pinfunction "1_1") (pintype "passive"))
      (node (ref "RC") (pin "1") (pinfunction "1_1") (pintype "passive"))
      (node (ref "SJ1") (pin "2") (pinfunction "2_2") (pintype "passive"))
      (node (ref "TO3.3V") (pin "2") (pinfunction "OUT1_2") (pintype "power_in"))
      (node (ref "TO3.3V") (pin "4") (pinfunction "OUT2_4") (pintype "power_in"))
      (node (ref "U$13") (pin "VDD") (pinfunction "11_VDD_VDD") (pintype "bidirectional"))
      (node (ref "U$8") (pin "P6") (pinfunction "VDDIO_P6") (pintype "bidirectional"))
      (node (ref "U$8") (pin "P8") (pinfunction "VDD_P8") (pintype "bidirectional"))
      (node (ref "X1") (pin "1") (pinfunction "1_1") (pintype "passive"))
    )
    (net (code "141") (name "VDD5") (class "Default")
      (node (ref "47UH") (pin "P$2") (pinfunction "2_P$2") (pintype "bidirectional"))
      (node (ref "C22") (pin "1") (pinfunction "1_1") (pintype "passive"))
      (node (ref "C26") (pin "1") (pinfunction "1_1") (pintype "passive"))
      (node (ref "C35") (pin "1") (pinfunction "1_1") (pintype "passive"))
      (node (ref "D2") (pin "C") (pinfunction "C_C") (pintype "passive"))
      (node (ref "JP5") (pin "1") (pinfunction "1_1") (pintype "passive"))
      (node (ref "R31") (pin "2") (pinfunction "2_2") (pintype "passive"))
      (node (ref "R32") (pin "2") (pinfunction "2_2") (pintype "passive"))
      (node (ref "R33") (pin "2") (pinfunction "2_2") (pintype "passive"))
      (node (ref "R34") (pin "2") (pinfunction "2_2") (pintype "passive"))
      (node (ref "TO3.3V") (pin "3") (pinfunction "IN_3") (pintype "power_in"))
      (node (ref "U$7") (pin "4") (pinfunction "4_4") (pintype "bidirectional"))
    )
    (net (code "142") (name "unconnected-(IC2-Pad1)") (class "Default")
      (node (ref "IC2") (pin "1") (pinfunction "1_1") (pintype "bidirectional"))
    )
    (net (code "143") (name "unconnected-(IC2-Pad2)") (class "Default")
      (node (ref "IC2") (pin "2") (pinfunction "2_2") (pintype "bidirectional"))
    )
    (net (code "144") (name "unconnected-(IC2-Pad3)") (class "Default")
      (node (ref "IC2") (pin "3") (pinfunction "3_3") (pintype "bidirectional"))
    )
    (net (code "145") (name "unconnected-(IC2-Pad4)") (class "Default")
      (node (ref "IC2") (pin "4") (pinfunction "4_4") (pintype "bidirectional"))
    )
    (net (code "146") (name "unconnected-(IC2-Pad5)") (class "Default")
      (node (ref "IC2") (pin "5") (pinfunction "5_5") (pintype "bidirectional"))
    )
    (net (code "147") (name "unconnected-(IC2-Pad6)") (class "Default")
      (node (ref "IC2") (pin "6") (pinfunction "6_6") (pintype "bidirectional"))
    )
    (net (code "148") (name "unconnected-(IC2-Pad7)") (class "Default")
      (node (ref "IC2") (pin "7") (pinfunction "7_7") (pintype "bidirectional"))
    )
    (net (code "149") (name "unconnected-(IC2-Pad9)") (class "Default")
      (node (ref "IC2") (pin "9") (pinfunction "9_9") (pintype "bidirectional"))
    )
    (net (code "150") (name "unconnected-(IC2-Pad11)") (class "Default")
      (node (ref "IC2") (pin "11") (pinfunction "11_11") (pintype "bidirectional"))
    )
    (net (code "151") (name "unconnected-(IC2-Pad14)") (class "Default")
      (node (ref "IC2") (pin "14") (pinfunction "14_14") (pintype "bidirectional"))
    )
    (net (code "152") (name "unconnected-(IC2-Pad15)") (class "Default")
      (node (ref "IC2") (pin "15") (pinfunction "15_15") (pintype "bidirectional"))
    )
    (net (code "153") (name "unconnected-(IC2-Pad16)") (class "Default")
      (node (ref "IC2") (pin "16") (pinfunction "16_16") (pintype "bidirectional"))
    )
    (net (code "154") (name "unconnected-(IC2-Pad17)") (class "Default")
      (node (ref "IC2") (pin "17") (pinfunction "17_17") (pintype "bidirectional"))
    )
    (net (code "155") (name "unconnected-(IC2-Pad19)") (class "Default")
      (node (ref "IC2") (pin "19") (pinfunction "19_19") (pintype "bidirectional"))
    )
    (net (code "156") (name "unconnected-(IC2-Pad21)") (class "Default")
      (node (ref "IC2") (pin "21") (pinfunction "21_21") (pintype "bidirectional"))
    )
    (net (code "157") (name "unconnected-(U$8-CSB-PadP2)") (class "Default")
      (node (ref "U$8") (pin "P2") (pinfunction "CSB_P2") (pintype "bidirectional"))
    )
    (net (code "158") (name "unconnected-(USB-PGH1-PadP$1)") (class "Default")
      (node (ref "USB") (pin "P$1") (pinfunction "PGH1_P$1") (pintype "bidirectional"))
    )
    (net (code "159") (name "unconnected-(USB-PGH2-PadP$2)") (class "Default")
      (node (ref "USB") (pin "P$2") (pinfunction "PGH2_P$2") (pintype "bidirectional"))
    )
    (net (code "160") (name "unconnected-(USB-PGH3-PadP$3)") (class "Default")
      (node (ref "USB") (pin "P$3") (pinfunction "PGH3_P$3") (pintype "bidirectional"))
    )
    (net (code "161") (name "unconnected-(USB-PGH4-PadP$4)") (class "Default")
      (node (ref "USB") (pin "P$4") (pinfunction "PGH4_P$4") (pintype "bidirectional"))
    )
    (net (code "162") (name "unconnected-(USB-Pad4)") (class "Default")
      (node (ref "USB") (pin "4") (pinfunction "4_4") (pintype "passive"))
    )
    (net (code "163") (name "unconnected-(X1-Pad7)") (class "Default")
      (node (ref "X1") (pin "7") (pinfunction "7_7") (pintype "passive"))
    )
    (net (code "164") (name "unconnected-(X1-Pad9)") (class "Default")
      (node (ref "X1") (pin "9") (pinfunction "9_9") (pintype "passive"))
    )
  )
)
